# SensorBoard.net
KiCad netlist of a schematic drawn in EAGLE
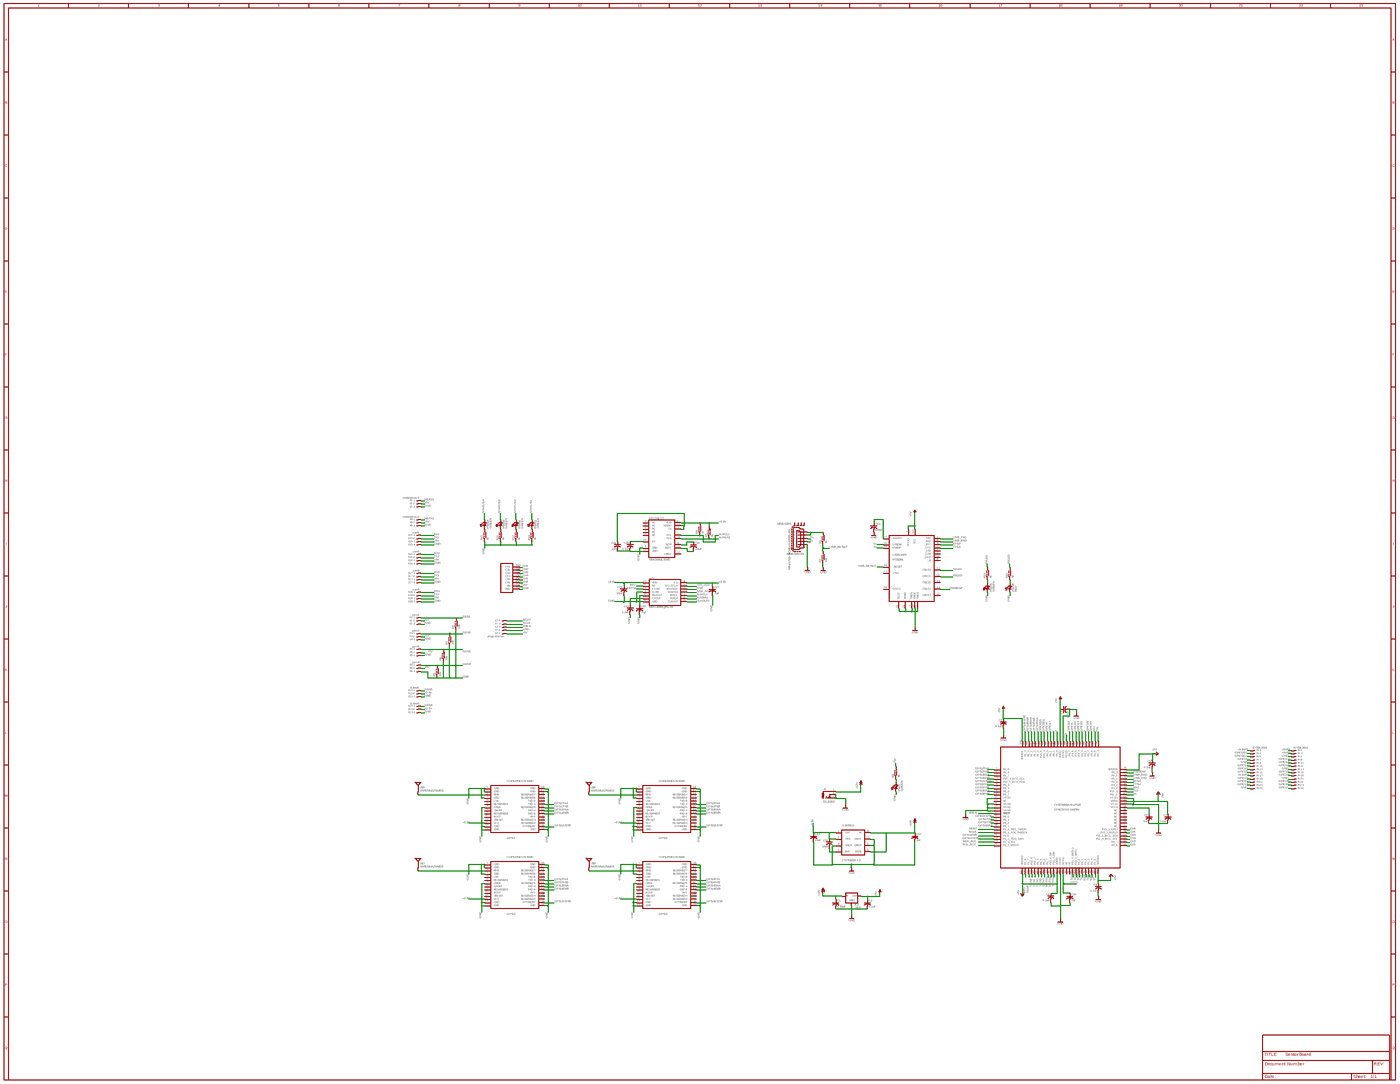
[diagram p0: schematic, sheet 1, overview]
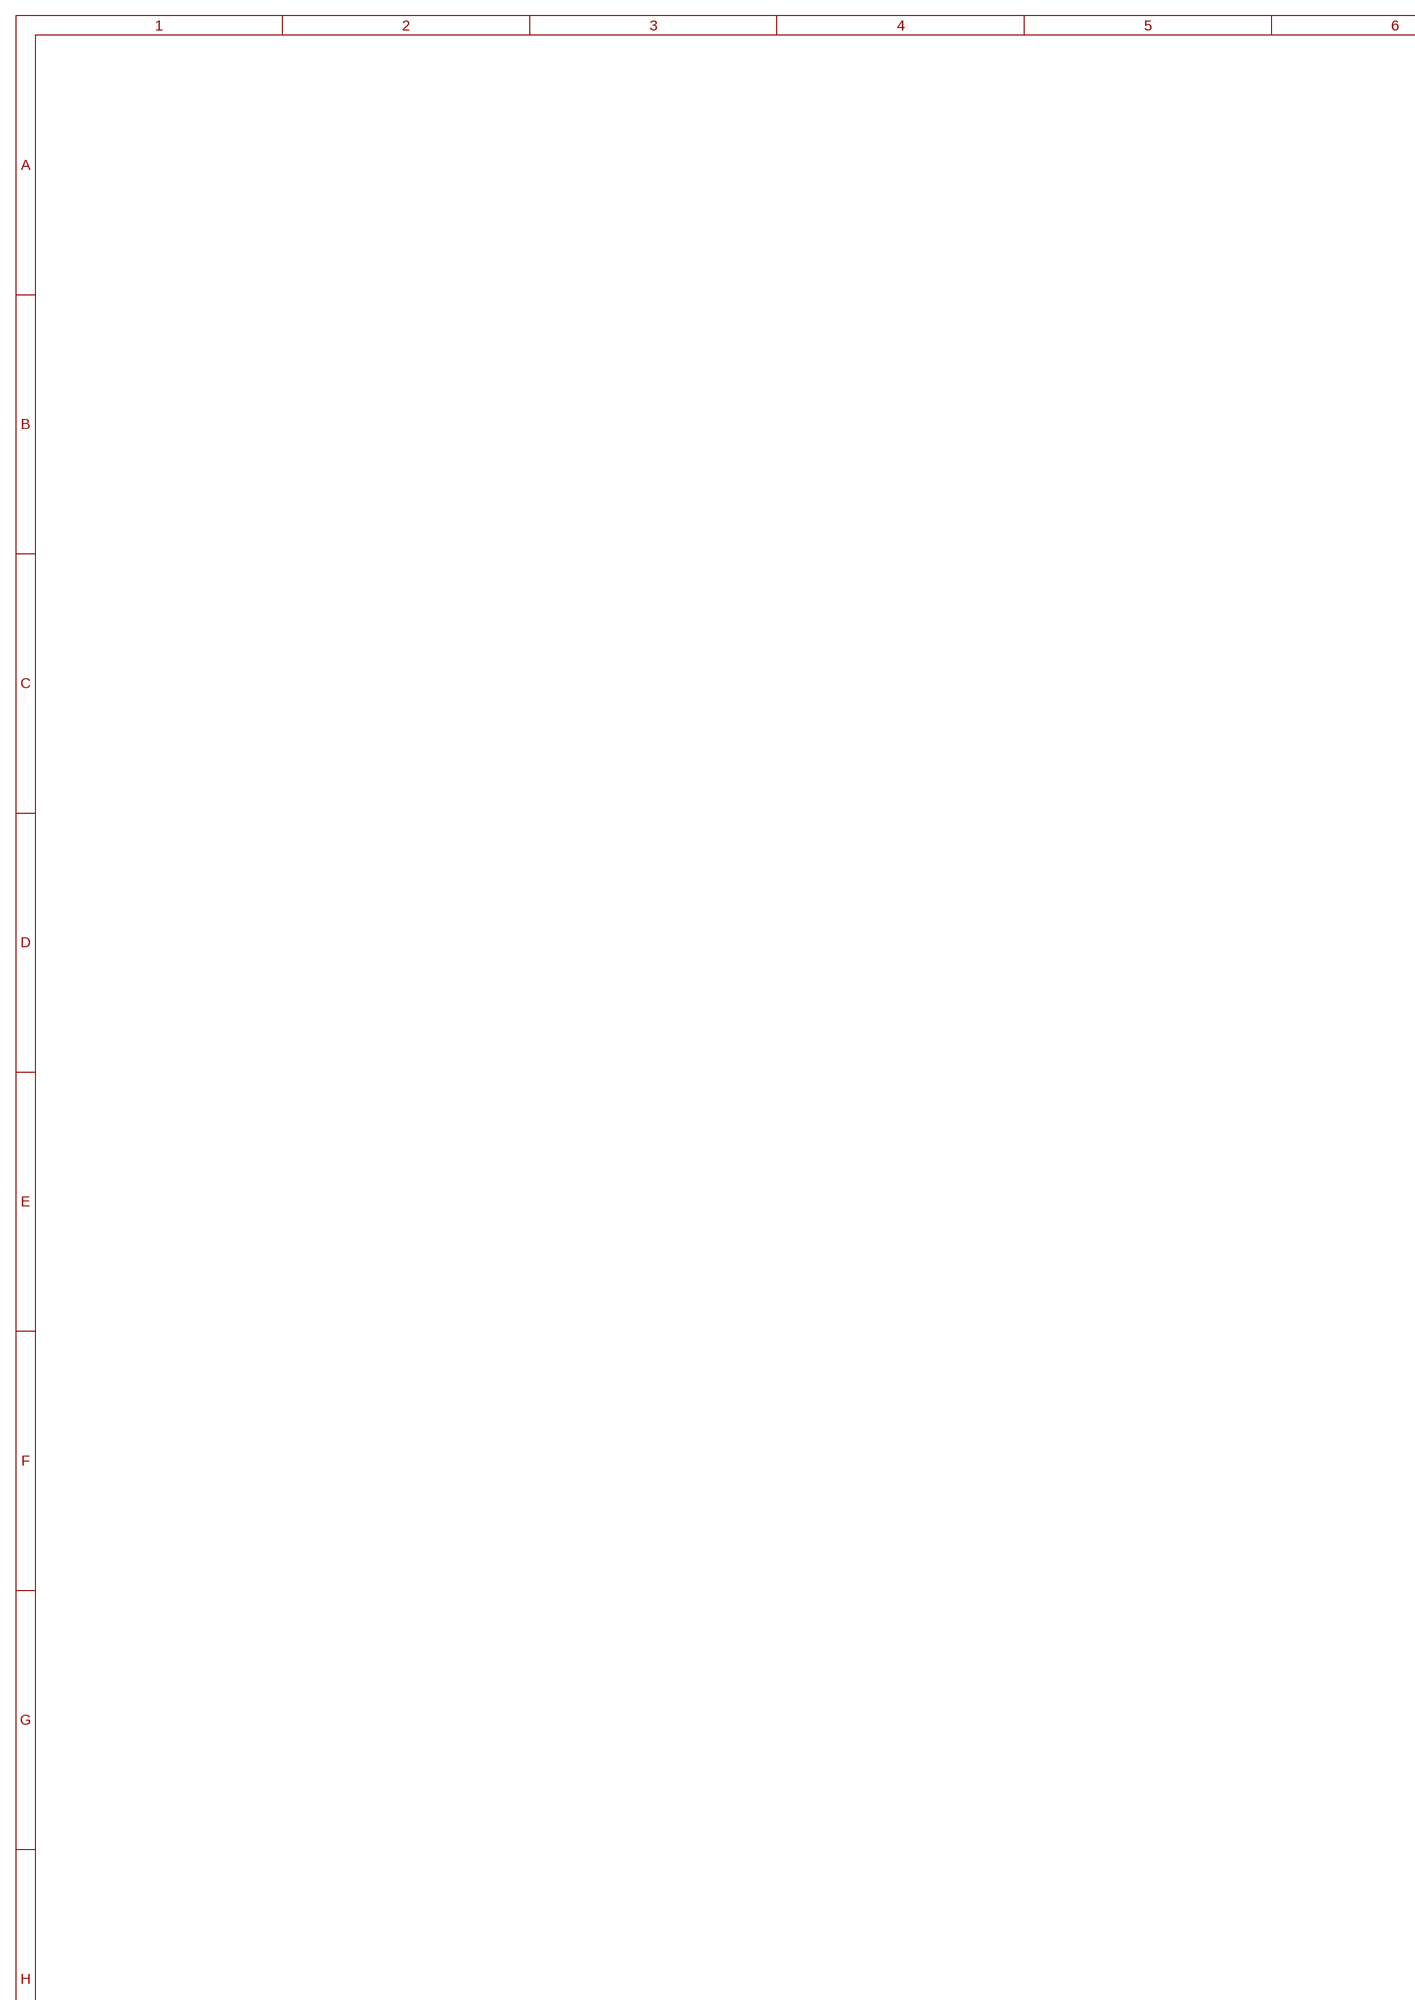
[diagram p1: schematic, sheet 1, part 1 of 8]
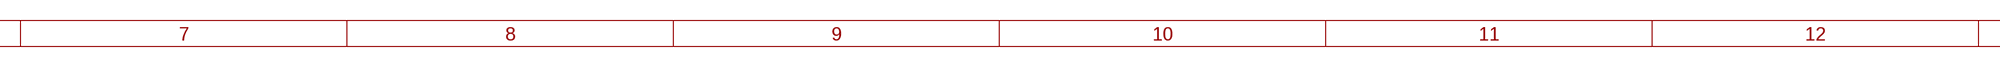
[diagram p2: schematic, sheet 1, part 2 of 8]
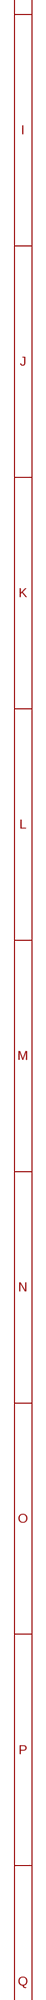
[diagram p3: schematic, sheet 1, part 3 of 8]
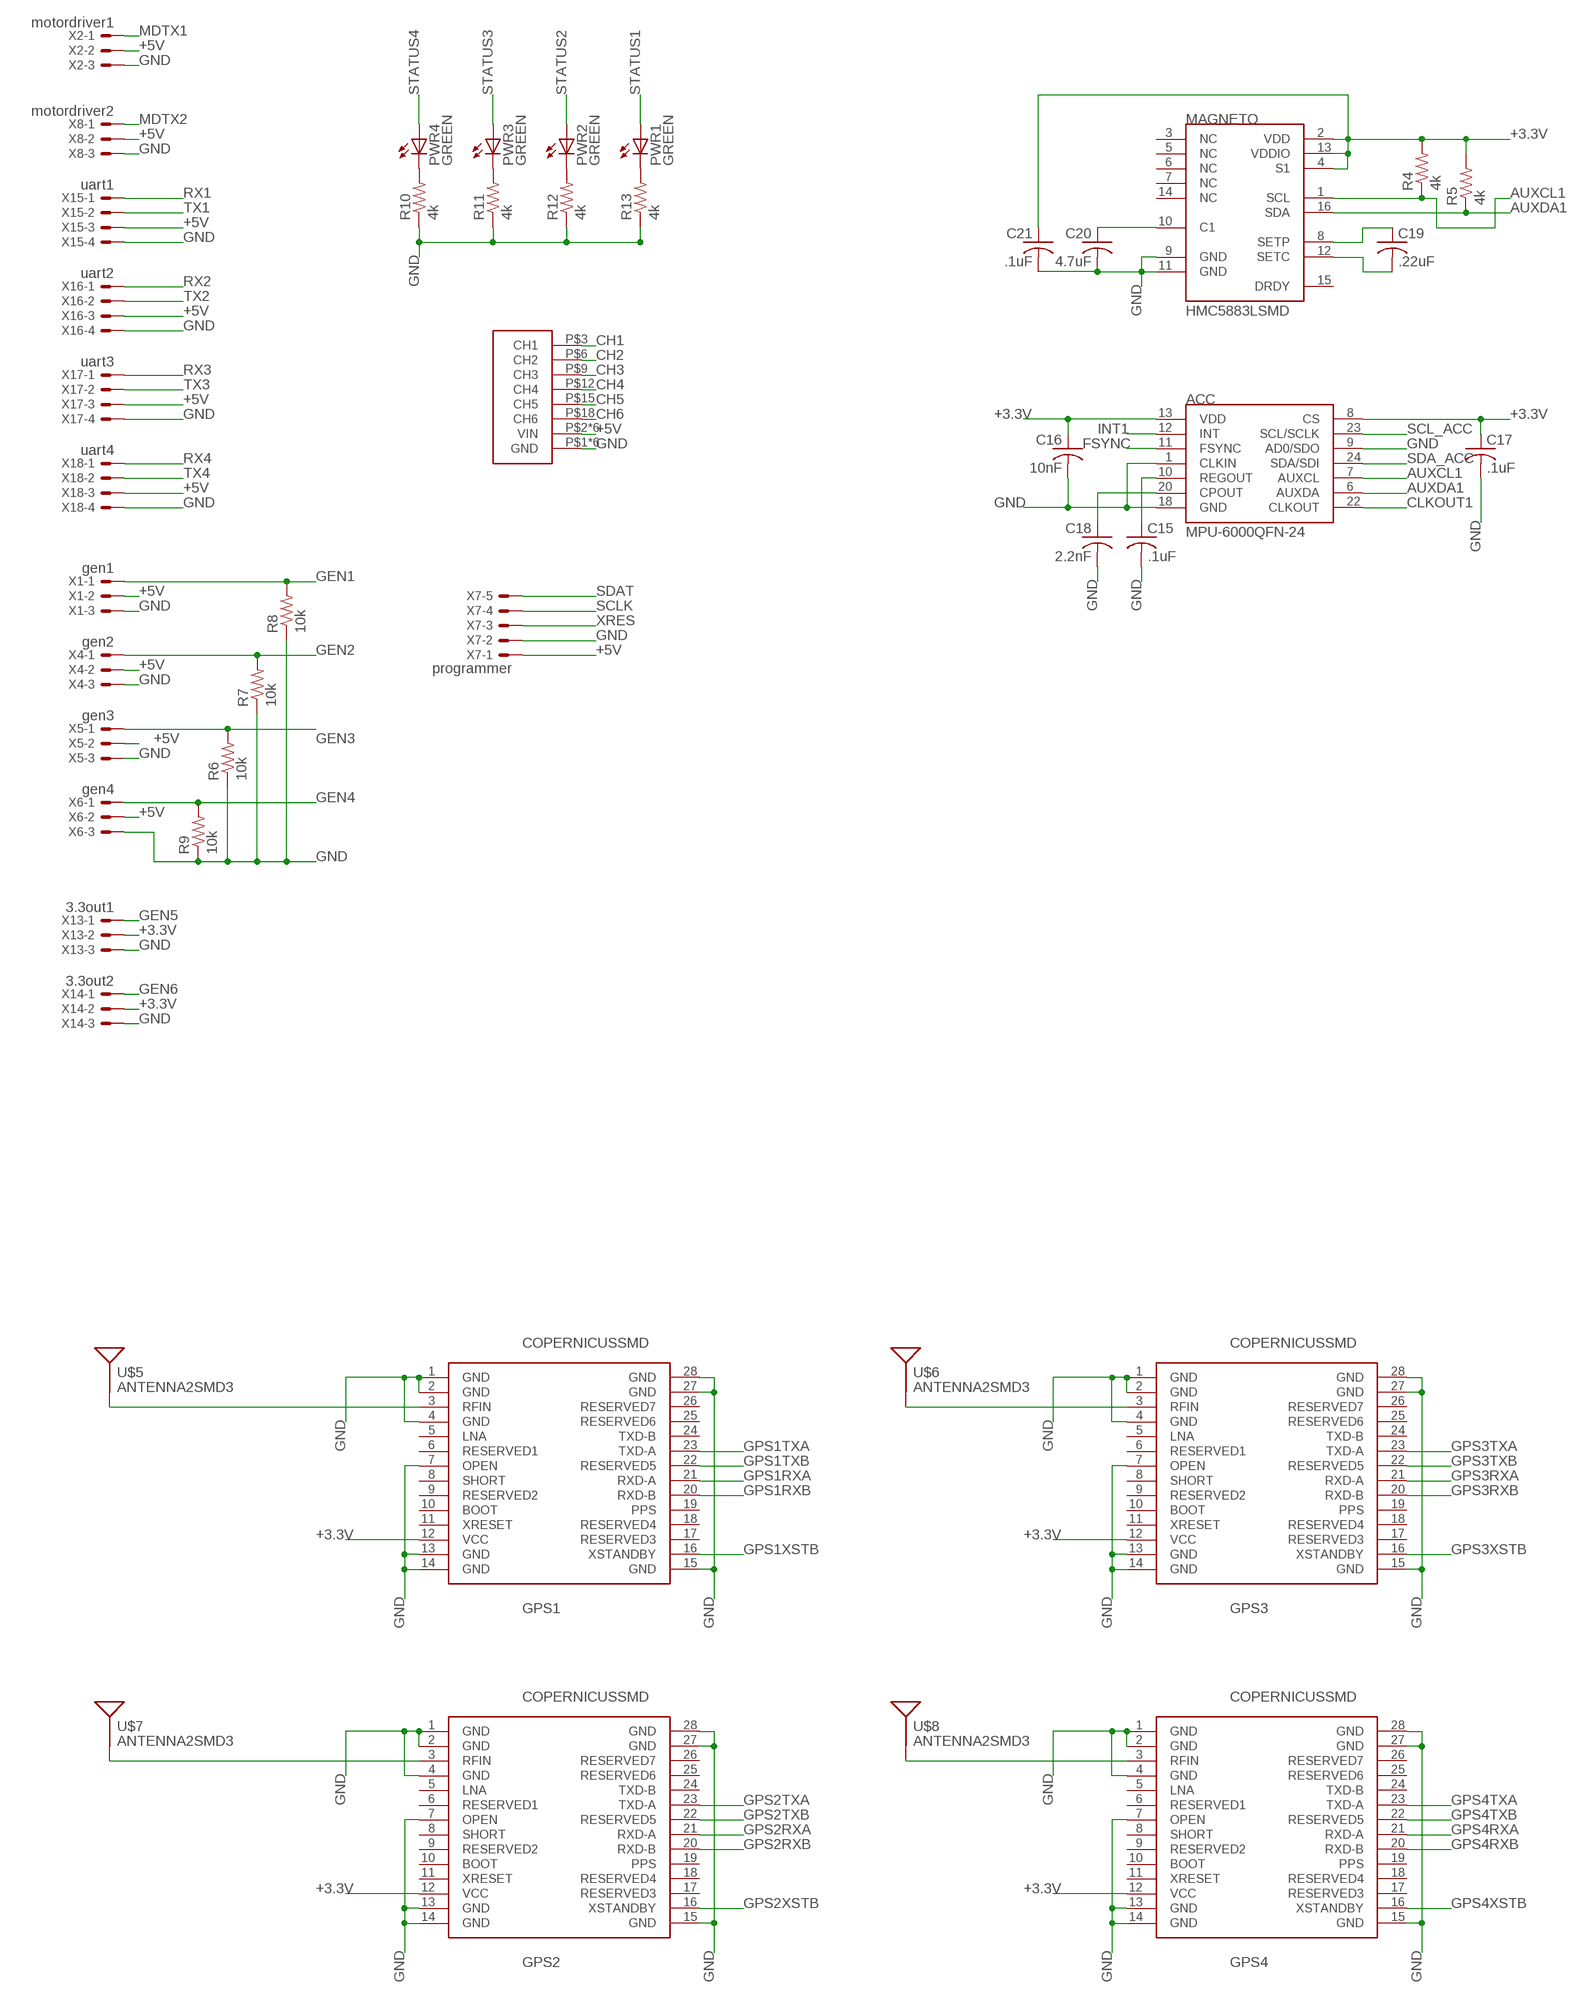
[diagram p4: schematic, sheet 1, part 4 of 8]
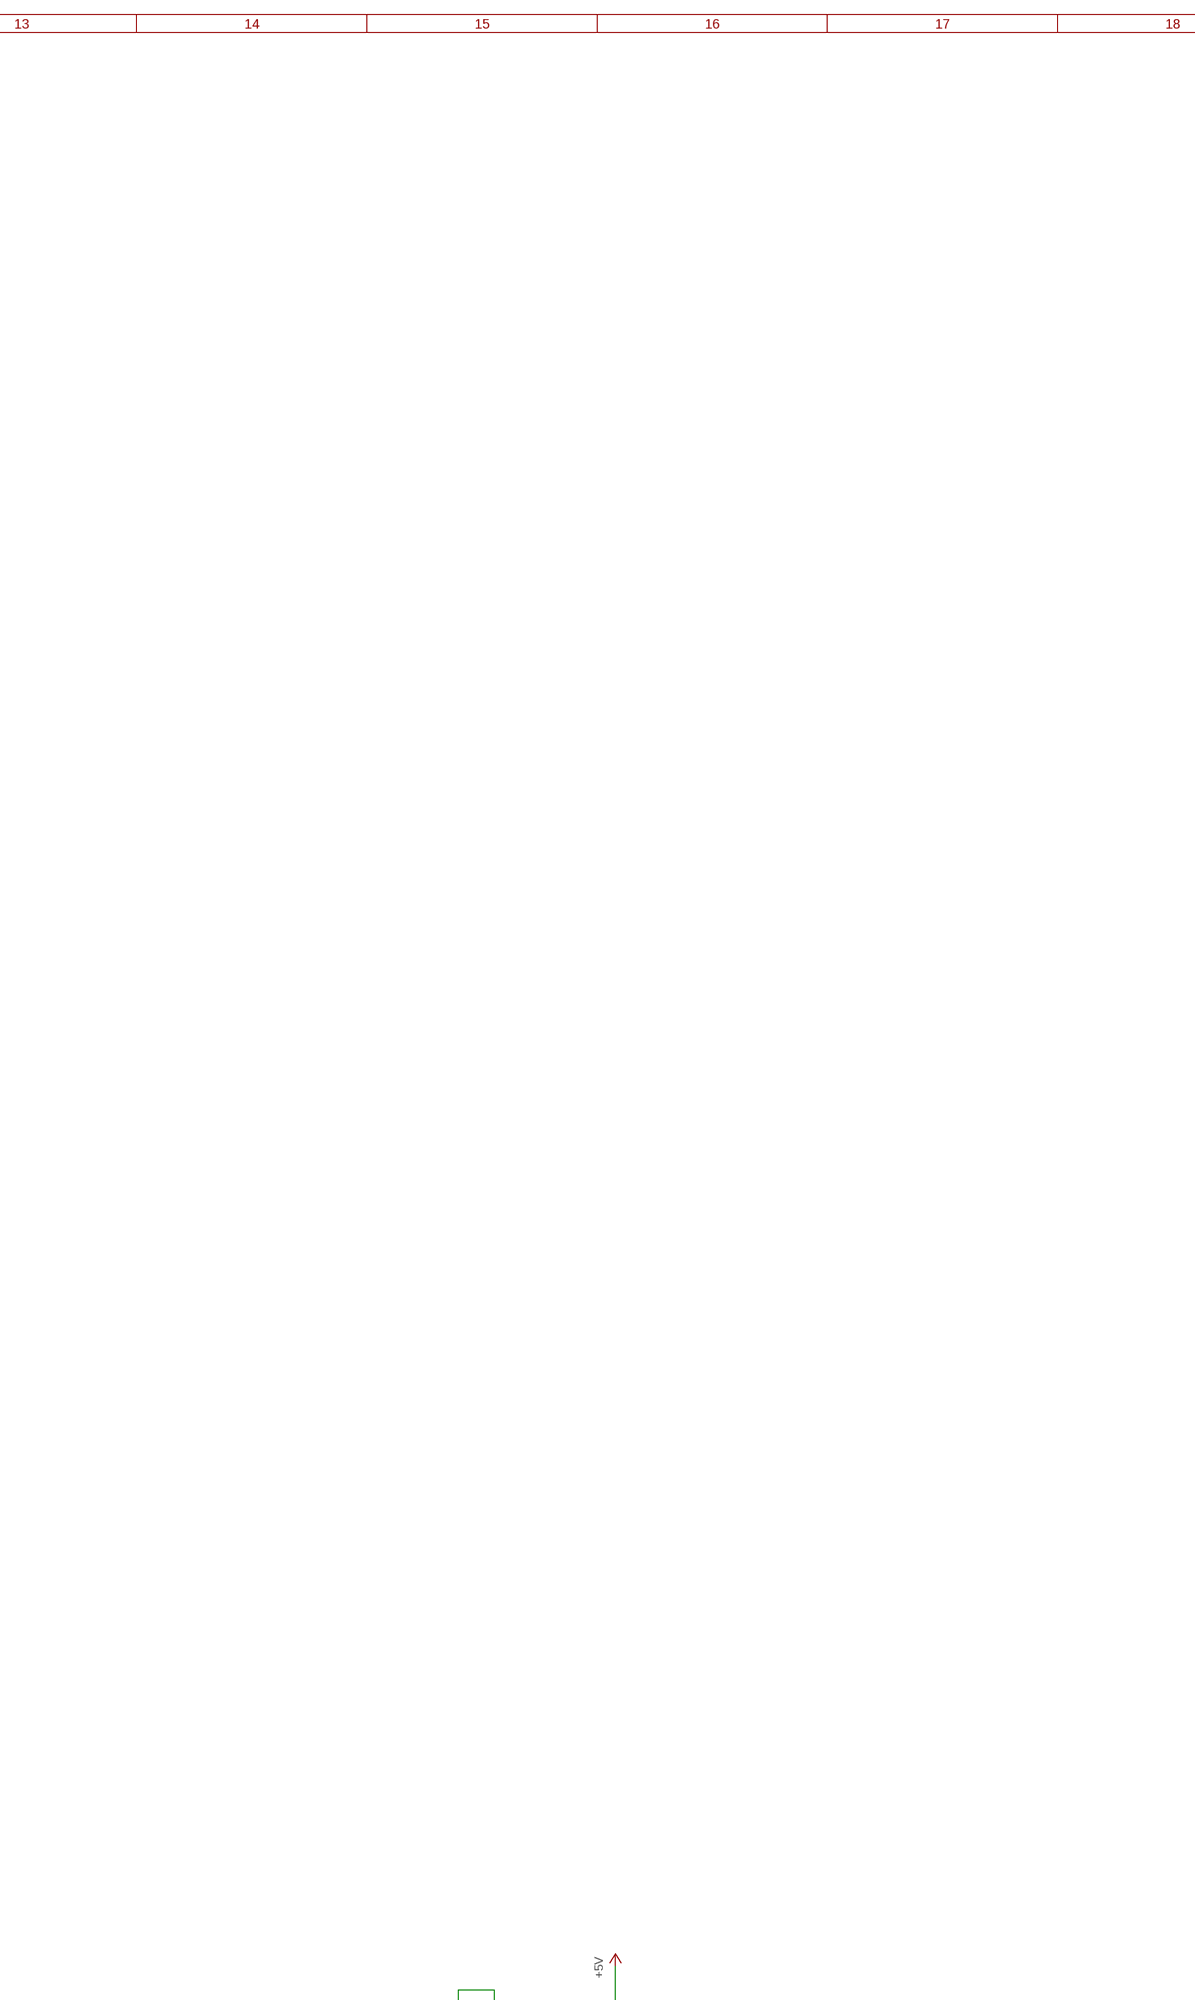
[diagram p5: schematic, sheet 1, part 5 of 8]
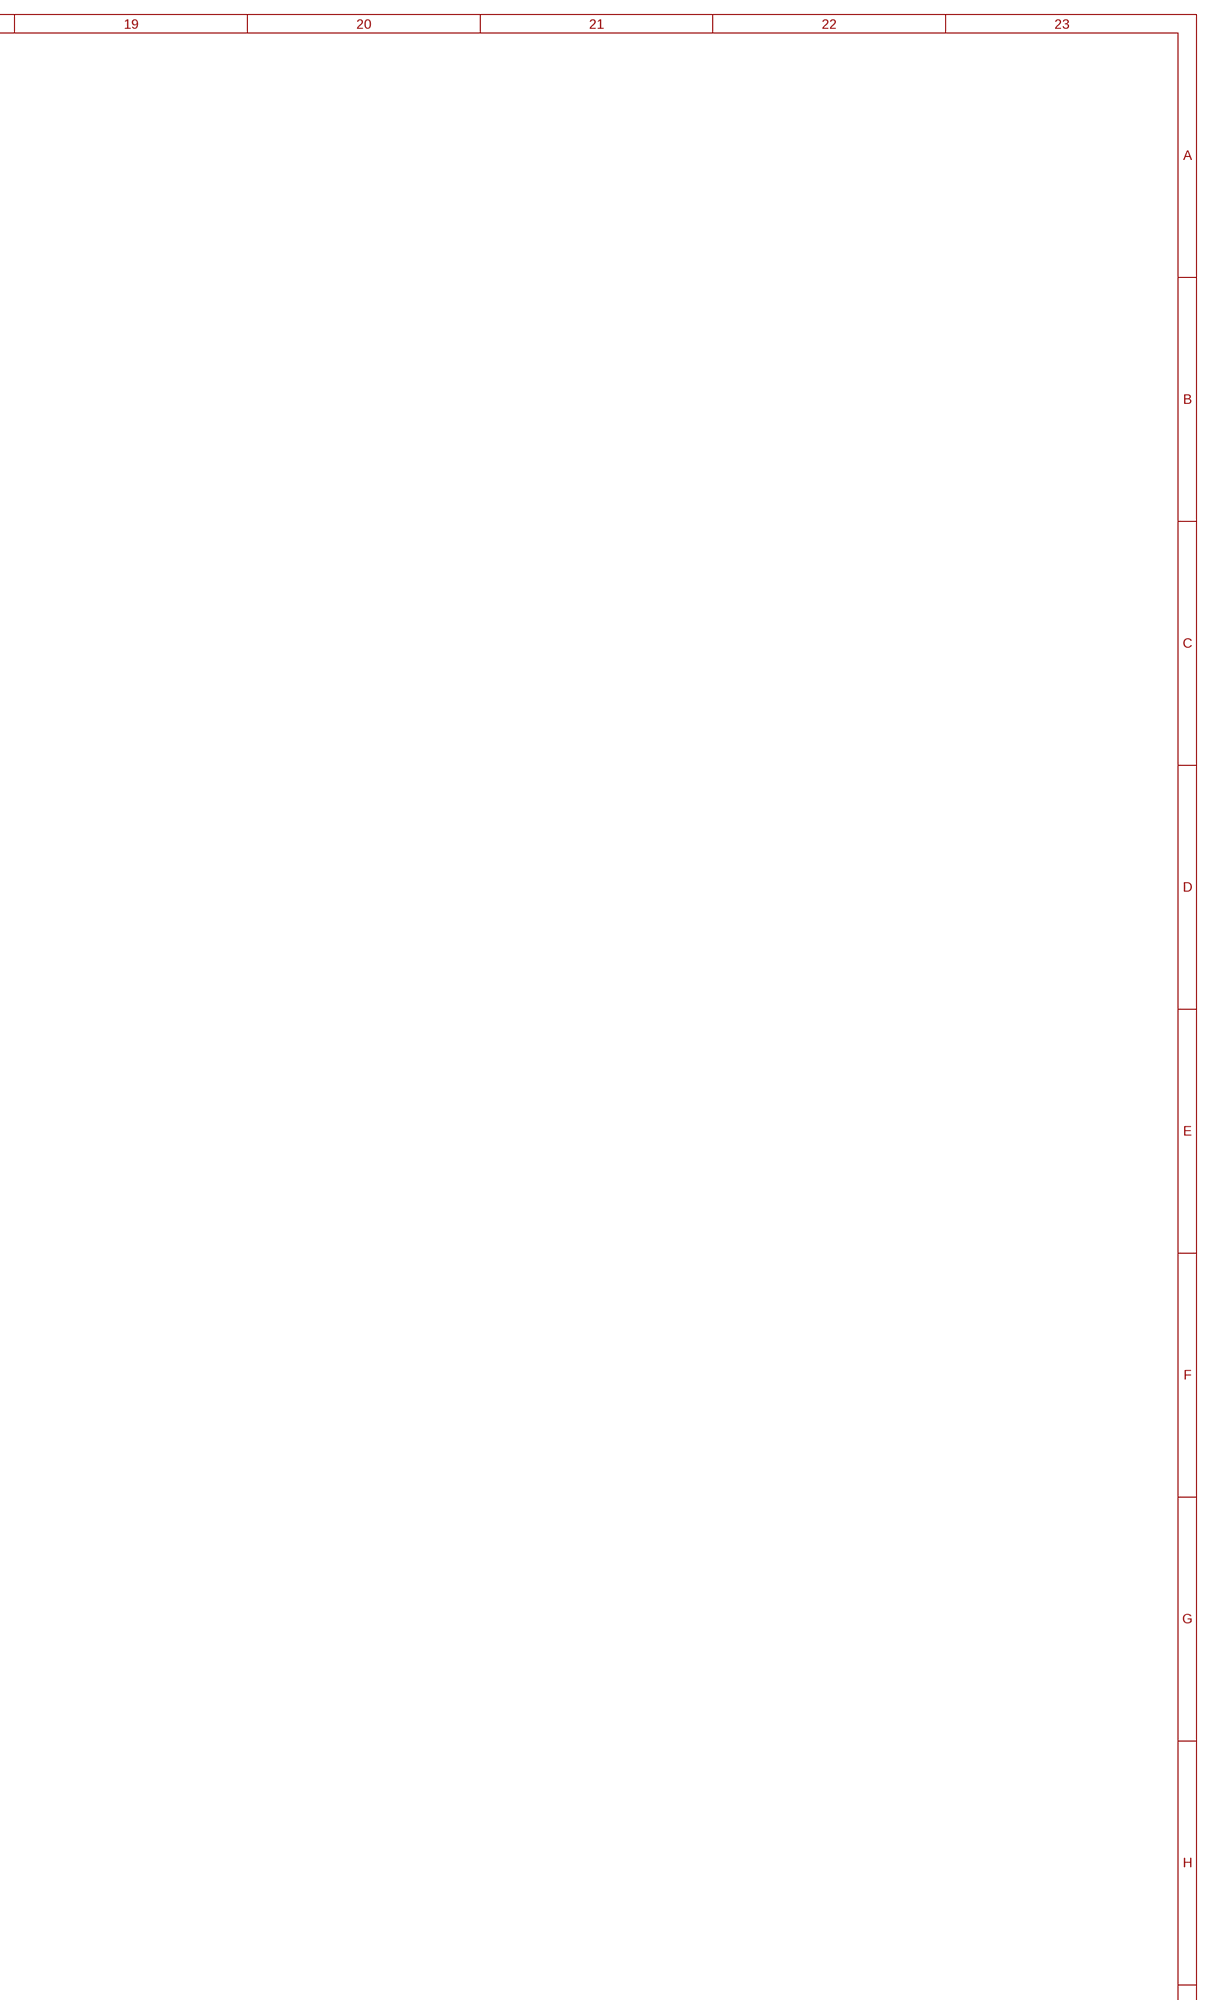
[diagram p6: schematic, sheet 1, part 6 of 8]
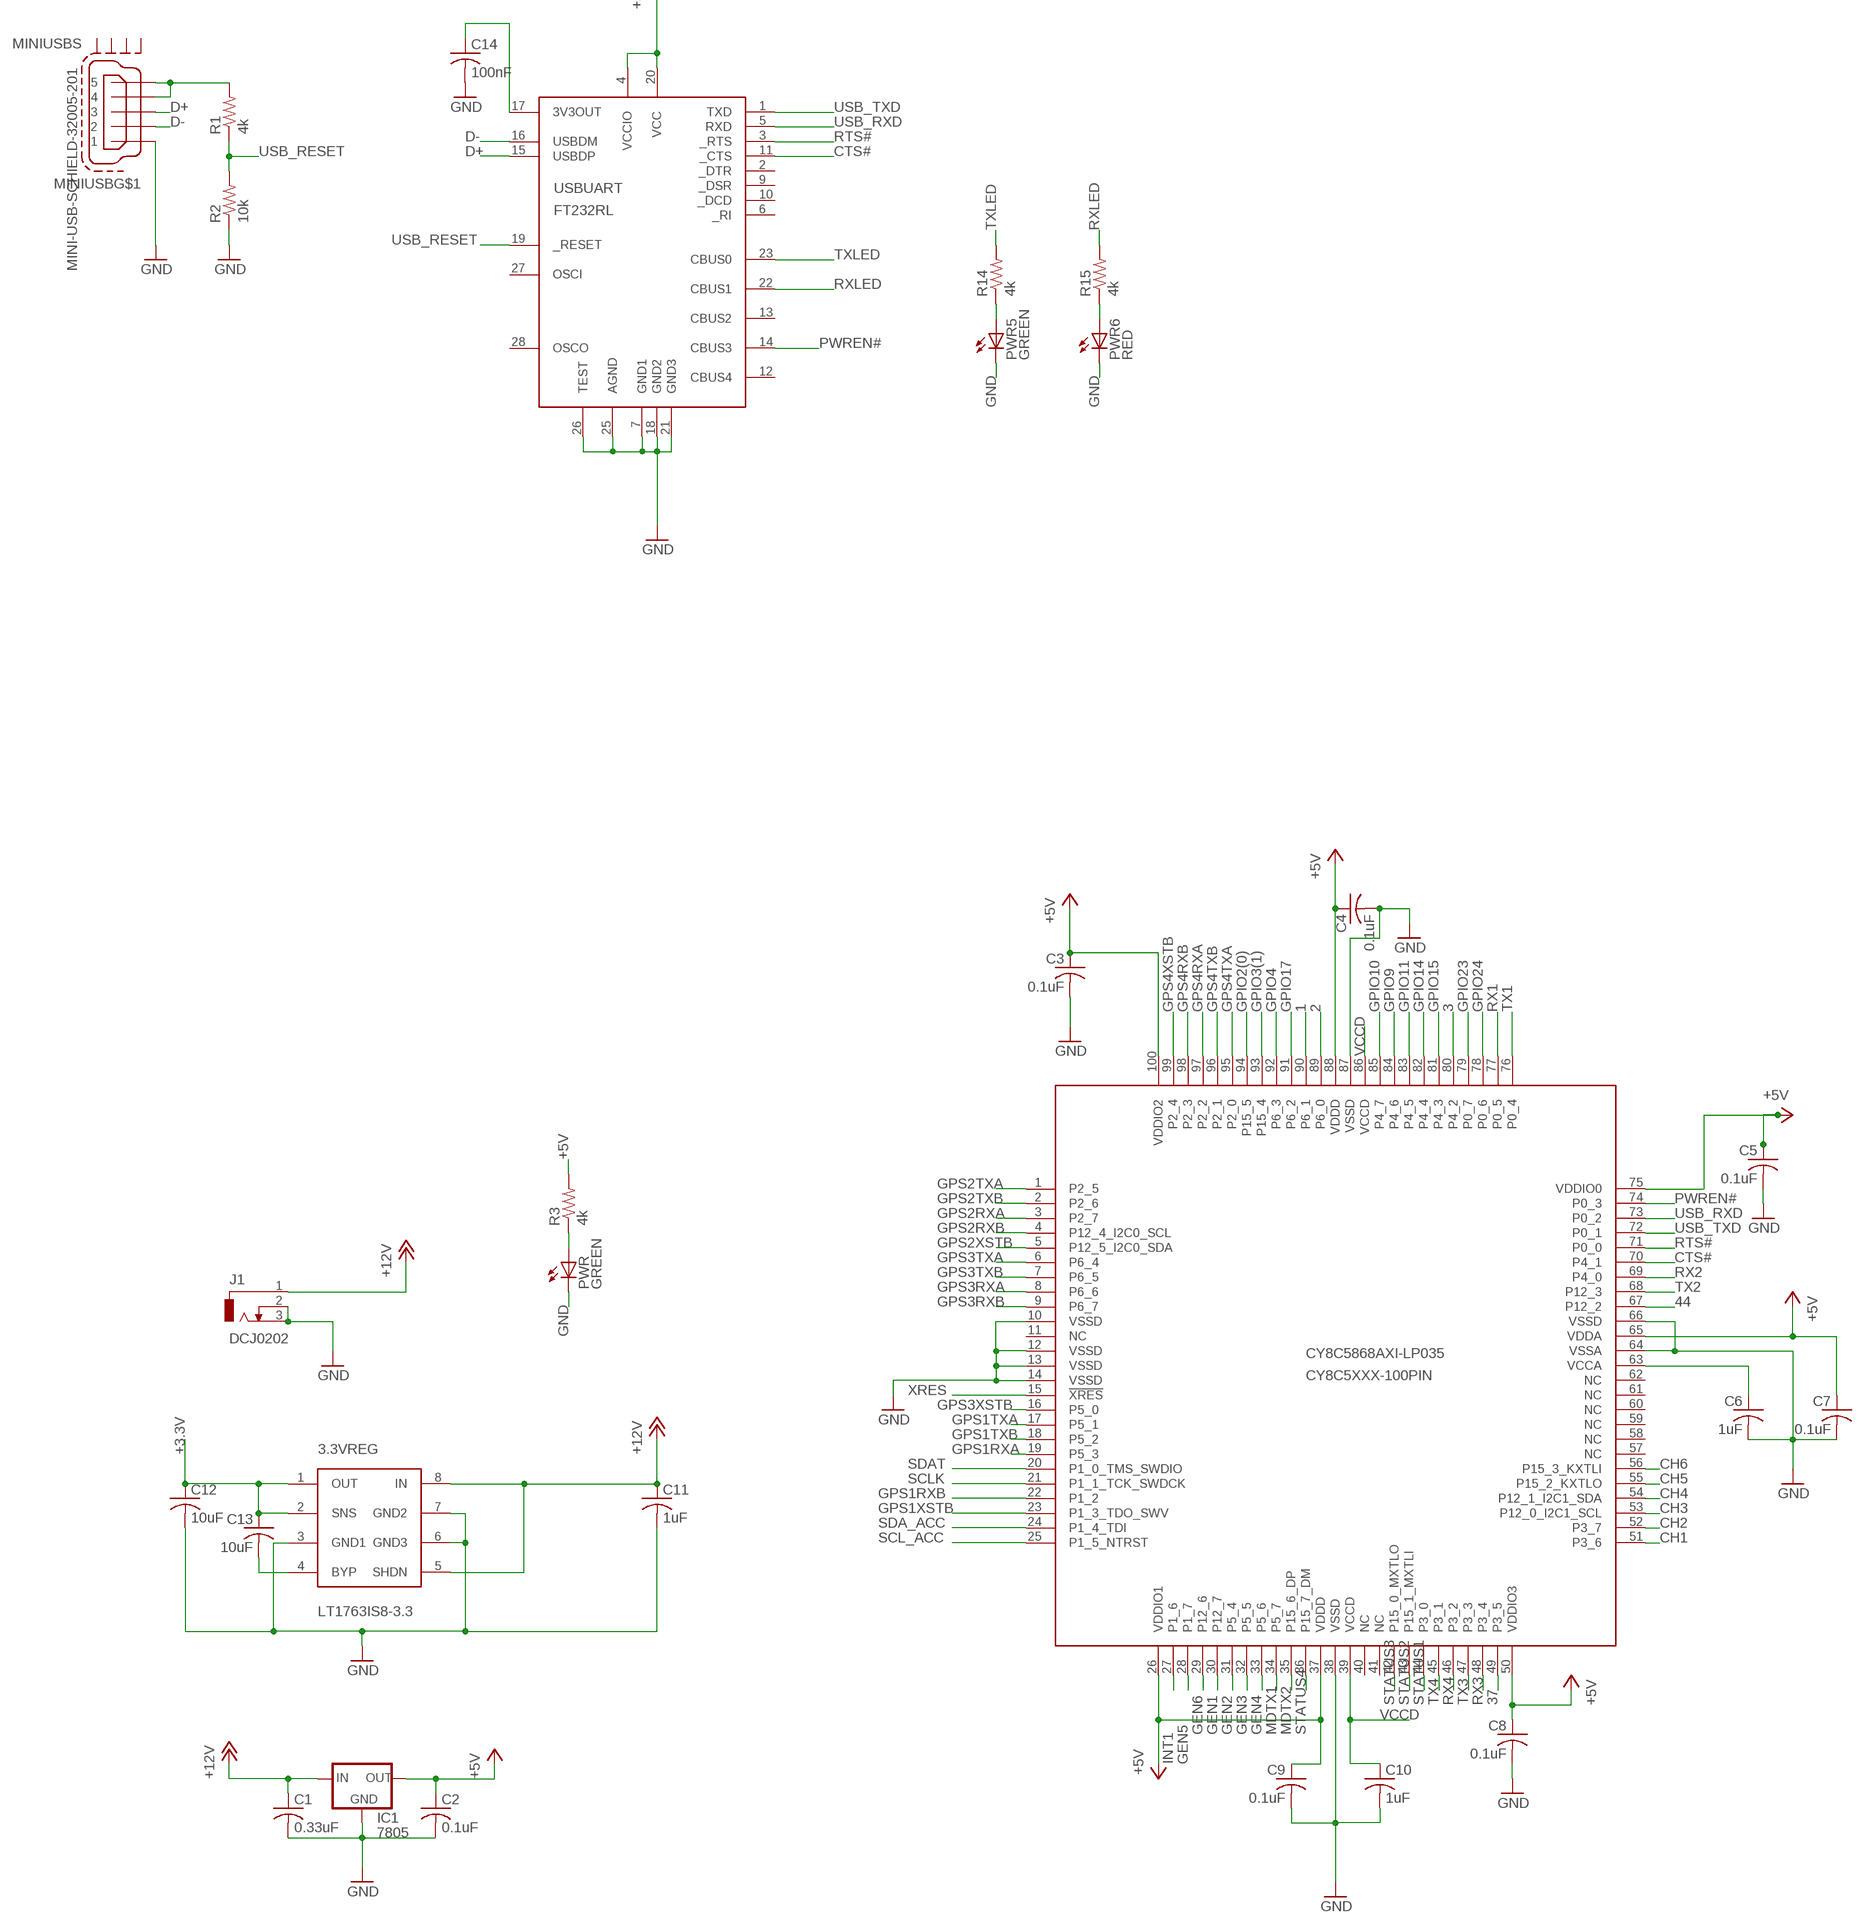
[diagram p7: schematic, sheet 1, part 7 of 8]
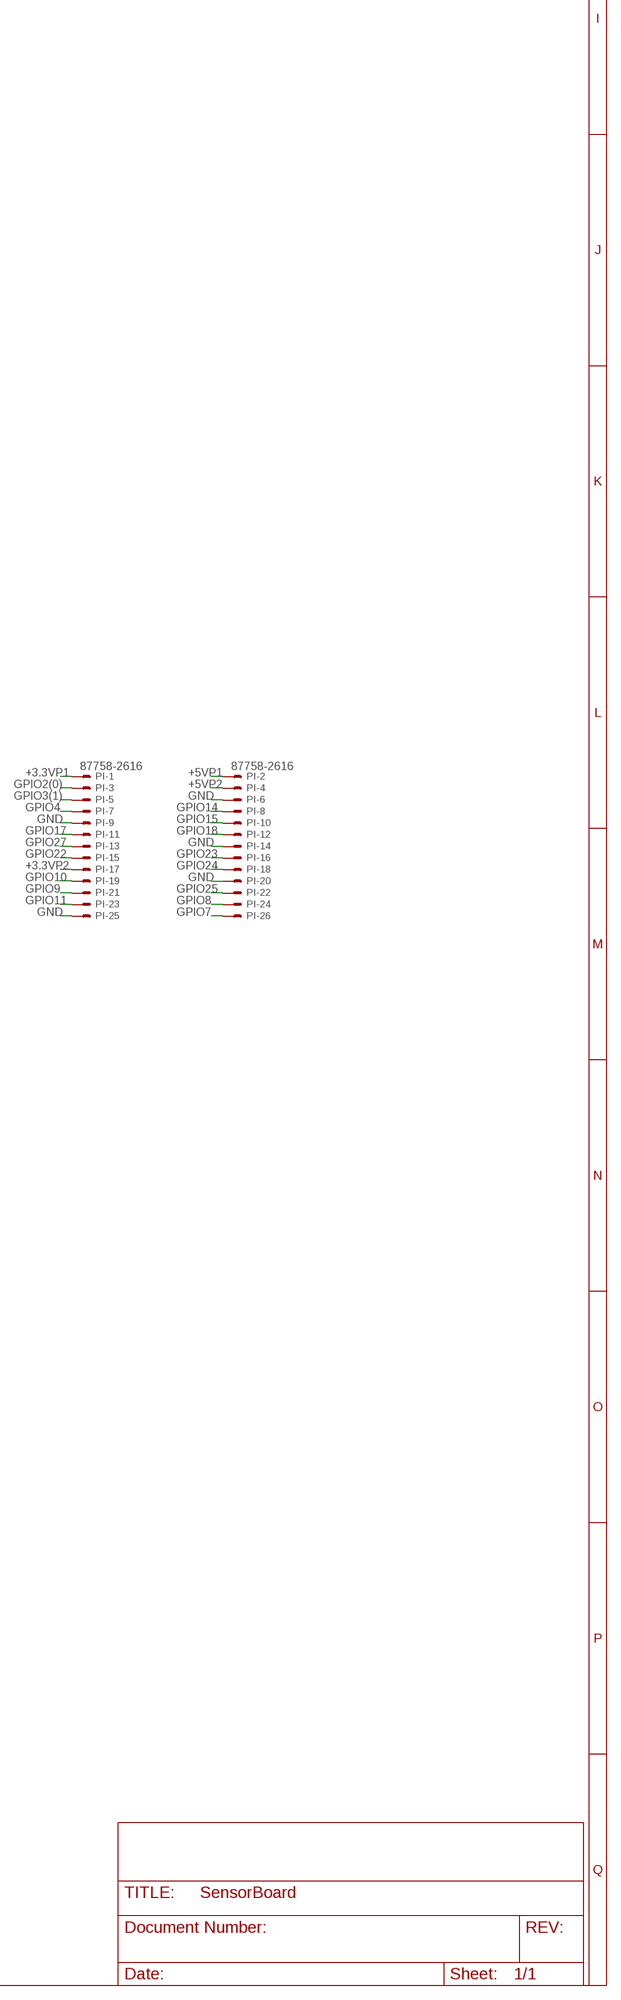
[diagram p8: schematic, sheet 1, part 8 of 8]

(export (version "E")
  (design (tool "Eeschema 10.0.6"))
  (components
    (comp (ref "3.3VREG")
      (value "LT1763IS8-3.3")
      (footprint "eagle-import:LT1763IS8-SMD")
      (libsource (lib "eagle-import") (part "LT1763IS8"))
    )
    (comp (ref "ACC")
      (value "MPU-6000QFN-24")
      (footprint "eagle-import:QFN-24-TESTING")
      (libsource (lib "eagle-import") (part "MPU-6000QFN-24"))
    )
    (comp (ref "C1")
      (value "0.33uF")
      (footprint "eagle-import:C0402")
      (libsource (lib "eagle-import") (part "C-USC0402"))
    )
    (comp (ref "C2")
      (value "0.1uF")
      (footprint "eagle-import:C0402")
      (libsource (lib "eagle-import") (part "C-USC0402"))
    )
    (comp (ref "C3")
      (value "0.1uF")
      (footprint "eagle-import:C0402")
      (libsource (lib "eagle-import") (part "C-USC0402"))
    )
    (comp (ref "C4")
      (value "0.1uF")
      (footprint "eagle-import:C0402")
      (libsource (lib "eagle-import") (part "C-USC0402"))
    )
    (comp (ref "C5")
      (value "0.1uF")
      (footprint "eagle-import:C0402")
      (libsource (lib "eagle-import") (part "C-USC0402"))
    )
    (comp (ref "C6")
      (value "1uF")
      (footprint "eagle-import:C0402")
      (libsource (lib "eagle-import") (part "C-USC0402"))
    )
    (comp (ref "C7")
      (value "0.1uF")
      (footprint "eagle-import:C0402")
      (libsource (lib "eagle-import") (part "C-USC0402"))
    )
    (comp (ref "C8")
      (value "0.1uF")
      (footprint "eagle-import:C0402")
      (libsource (lib "eagle-import") (part "C-USC0402"))
    )
    (comp (ref "C9")
      (value "0.1uF")
      (footprint "eagle-import:C0402")
      (libsource (lib "eagle-import") (part "C-USC0402"))
    )
    (comp (ref "C10")
      (value "1uF")
      (footprint "eagle-import:C0402")
      (libsource (lib "eagle-import") (part "C-USC0402"))
    )
    (comp (ref "C11")
      (value "1uF")
      (footprint "eagle-import:C0402")
      (libsource (lib "eagle-import") (part "C-USC0402"))
    )
    (comp (ref "C12")
      (value "10uF")
      (footprint "eagle-import:C0402")
      (libsource (lib "eagle-import") (part "C-USC0402"))
    )
    (comp (ref "C13")
      (value "10uF")
      (footprint "eagle-import:C0402")
      (libsource (lib "eagle-import") (part "C-USC0402"))
    )
    (comp (ref "C14")
      (value "100nF")
      (footprint "eagle-import:C0402")
      (libsource (lib "eagle-import") (part "C-USC0402"))
    )
    (comp (ref "C15")
      (value ".1uF")
      (footprint "eagle-import:C0402")
      (libsource (lib "eagle-import") (part "C-USC0402"))
    )
    (comp (ref "C16")
      (value "10nF")
      (footprint "eagle-import:C0402")
      (libsource (lib "eagle-import") (part "C-USC0402"))
    )
    (comp (ref "C17")
      (value ".1uF")
      (footprint "eagle-import:C0402")
      (libsource (lib "eagle-import") (part "C-USC0402"))
    )
    (comp (ref "C18")
      (value "2.2nF")
      (footprint "eagle-import:C0402")
      (libsource (lib "eagle-import") (part "C-USC0402"))
    )
    (comp (ref "C19")
      (value ".22uF")
      (footprint "eagle-import:C0402")
      (libsource (lib "eagle-import") (part "C-USC0402"))
    )
    (comp (ref "C20")
      (value "4.7uF")
      (footprint "eagle-import:C0402")
      (libsource (lib "eagle-import") (part "C-USC0402"))
    )
    (comp (ref "C21")
      (value ".1uF")
      (footprint "eagle-import:C0402")
      (libsource (lib "eagle-import") (part "C-USC0402"))
    )
    (comp (ref "CY8C5868AXI-LP035")
      (value "CY8C5XXX-100PIN")
      (footprint "eagle-import:TQFP-14X14-100")
      (fields (field (name "MPN") "CY8C5588AXI-060"))
      (libsource (lib "eagle-import") (part "CY8C5XXX-100PIN"))
    )
    (comp (ref "GPS1")
      (value "COPERNICUSSMD")
      (footprint "eagle-import:COPERNICUS")
      (libsource (lib "eagle-import") (part "COPERNICUSSMD"))
    )
    (comp (ref "GPS2")
      (value "COPERNICUSSMD")
      (footprint "eagle-import:COPERNICUS")
      (libsource (lib "eagle-import") (part "COPERNICUSSMD"))
    )
    (comp (ref "GPS3")
      (value "COPERNICUSSMD")
      (footprint "eagle-import:COPERNICUS")
      (libsource (lib "eagle-import") (part "COPERNICUSSMD"))
    )
    (comp (ref "GPS4")
      (value "COPERNICUSSMD")
      (footprint "eagle-import:COPERNICUS")
      (libsource (lib "eagle-import") (part "COPERNICUSSMD"))
    )
    (comp (ref "IC1")
      (value "7805")
      (footprint "eagle-import:78XXL")
      (libsource (lib "eagle-import") (part "78XXL"))
    )
    (comp (ref "J1")
      (value "DCJ0202")
      (footprint "eagle-import:DCJ0202")
      (libsource (lib "eagle-import") (part "DCJ0202"))
    )
    (comp (ref "MAGNETO")
      (value "HMC5883LSMD")
      (footprint "eagle-import:16LPCC")
      (libsource (lib "eagle-import") (part "HMC5883LSMD"))
    )
    (comp (ref "MINIUSB")
      (value "MINI-USB-SCHIELD-32005-201")
      (footprint "eagle-import:32005-201")
      (libsource (lib "eagle-import") (part "MINI-USB-SCHIELD-32005-201"))
    )
    (comp (ref "PI")
      (value "87758-2616")
      (footprint "eagle-import:87758-2616")
      (libsource (lib "eagle-import") (part "87758-2616"))
    )
    (comp (ref "PWR")
      (value "GREEN")
      (footprint "eagle-import:CHIP-LED0603")
      (libsource (lib "eagle-import") (part "LEDCHIP-LED0603"))
    )
    (comp (ref "PWR1")
      (value "GREEN")
      (footprint "eagle-import:CHIP-LED0603")
      (libsource (lib "eagle-import") (part "LEDCHIP-LED0603"))
    )
    (comp (ref "PWR2")
      (value "GREEN")
      (footprint "eagle-import:CHIP-LED0603")
      (libsource (lib "eagle-import") (part "LEDCHIP-LED0603"))
    )
    (comp (ref "PWR3")
      (value "GREEN")
      (footprint "eagle-import:CHIP-LED0603")
      (libsource (lib "eagle-import") (part "LEDCHIP-LED0603"))
    )
    (comp (ref "PWR4")
      (value "GREEN")
      (footprint "eagle-import:CHIP-LED0603")
      (libsource (lib "eagle-import") (part "LEDCHIP-LED0603"))
    )
    (comp (ref "PWR5")
      (value "GREEN")
      (footprint "eagle-import:CHIP-LED0603")
      (libsource (lib "eagle-import") (part "LEDCHIP-LED0603"))
    )
    (comp (ref "PWR6")
      (value "RED")
      (footprint "eagle-import:CHIP-LED0603")
      (libsource (lib "eagle-import") (part "LEDCHIP-LED0603"))
    )
    (comp (ref "R1")
      (value "4k")
      (footprint "eagle-import:0204_5")
      (libsource (lib "eagle-import") (part "R-US_0204/5"))
    )
    (comp (ref "R2")
      (value "10k")
      (footprint "eagle-import:0204_5")
      (libsource (lib "eagle-import") (part "R-US_0204/5"))
    )
    (comp (ref "R3")
      (value "4k")
      (footprint "eagle-import:0204_5")
      (libsource (lib "eagle-import") (part "R-US_0204/5"))
    )
    (comp (ref "R4")
      (value "4k")
      (footprint "eagle-import:0204_5")
      (libsource (lib "eagle-import") (part "R-US_0204/5"))
    )
    (comp (ref "R5")
      (value "4k")
      (footprint "eagle-import:0204_5")
      (libsource (lib "eagle-import") (part "R-US_0204/5"))
    )
    (comp (ref "R6")
      (value "10k")
      (footprint "eagle-import:0204_5")
      (libsource (lib "eagle-import") (part "R-US_0204/5"))
    )
    (comp (ref "R7")
      (value "10k")
      (footprint "eagle-import:0204_5")
      (libsource (lib "eagle-import") (part "R-US_0204/5"))
    )
    (comp (ref "R8")
      (value "10k")
      (footprint "eagle-import:0204_5")
      (libsource (lib "eagle-import") (part "R-US_0204/5"))
    )
    (comp (ref "R9")
      (value "10k")
      (footprint "eagle-import:0204_5")
      (libsource (lib "eagle-import") (part "R-US_0204/5"))
    )
    (comp (ref "R10")
      (value "4k")
      (footprint "eagle-import:0204_5")
      (libsource (lib "eagle-import") (part "R-US_0204/5"))
    )
    (comp (ref "R11")
      (value "4k")
      (footprint "eagle-import:0204_5")
      (libsource (lib "eagle-import") (part "R-US_0204/5"))
    )
    (comp (ref "R12")
      (value "4k")
      (footprint "eagle-import:0204_5")
      (libsource (lib "eagle-import") (part "R-US_0204/5"))
    )
    (comp (ref "R13")
      (value "4k")
      (footprint "eagle-import:0204_5")
      (libsource (lib "eagle-import") (part "R-US_0204/5"))
    )
    (comp (ref "R14")
      (value "4k")
      (footprint "eagle-import:0204_5")
      (libsource (lib "eagle-import") (part "R-US_0204/5"))
    )
    (comp (ref "R15")
      (value "4k")
      (footprint "eagle-import:0204_5")
      (libsource (lib "eagle-import") (part "R-US_0204/5"))
    )
    (comp (ref "RC")
      (value "6-CHANNEL")
      (footprint "eagle-import:6-CHANNEL")
      (libsource (lib "eagle-import") (part "6-CHANNEL"))
    )
    (comp (ref "U$5")
      (value "ANTENNA2SMD3")
      (footprint "eagle-import:ANTENNA-CHIP4")
      (libsource (lib "eagle-import") (part "ANTENNA2SMD3"))
    )
    (comp (ref "U$6")
      (value "ANTENNA2SMD3")
      (footprint "eagle-import:ANTENNA-CHIP4")
      (libsource (lib "eagle-import") (part "ANTENNA2SMD3"))
    )
    (comp (ref "U$7")
      (value "ANTENNA2SMD3")
      (footprint "eagle-import:ANTENNA-CHIP4")
      (libsource (lib "eagle-import") (part "ANTENNA2SMD3"))
    )
    (comp (ref "U$8")
      (value "ANTENNA2SMD3")
      (footprint "eagle-import:ANTENNA-CHIP4")
      (libsource (lib "eagle-import") (part "ANTENNA2SMD3"))
    )
    (comp (ref "USBUART")
      (value "FT232RL")
      (footprint "eagle-import:SSOP28DB")
      (libsource (lib "eagle-import") (part "FT232RL"))
    )
    (comp (ref "X1")
      (value "gen1")
      (footprint "eagle-import:KK-156-3")
      (libsource (lib "eagle-import") (part "KK-156-3"))
    )
    (comp (ref "X2")
      (value "motordriver1")
      (footprint "eagle-import:KK-156-3")
      (libsource (lib "eagle-import") (part "KK-156-3"))
    )
    (comp (ref "X4")
      (value "gen2")
      (footprint "eagle-import:KK-156-3")
      (libsource (lib "eagle-import") (part "KK-156-3"))
    )
    (comp (ref "X5")
      (value "gen3")
      (footprint "eagle-import:KK-156-3")
      (libsource (lib "eagle-import") (part "KK-156-3"))
    )
    (comp (ref "X6")
      (value "gen4")
      (footprint "eagle-import:KK-156-3")
      (libsource (lib "eagle-import") (part "KK-156-3"))
    )
    (comp (ref "X7")
      (value "programmer")
      (footprint "eagle-import:KK-156-5")
      (libsource (lib "eagle-import") (part "KK-156-5"))
    )
    (comp (ref "X8")
      (value "motordriver2")
      (footprint "eagle-import:KK-156-3")
      (libsource (lib "eagle-import") (part "KK-156-3"))
    )
    (comp (ref "X13")
      (value "3.3out1")
      (footprint "eagle-import:KK-156-3")
      (libsource (lib "eagle-import") (part "KK-156-3"))
    )
    (comp (ref "X14")
      (value "3.3out2")
      (footprint "eagle-import:KK-156-3")
      (libsource (lib "eagle-import") (part "KK-156-3"))
    )
    (comp (ref "X15")
      (value "uart1")
      (footprint "eagle-import:KK-156-4")
      (libsource (lib "eagle-import") (part "KK-156-4"))
    )
    (comp (ref "X16")
      (value "uart2")
      (footprint "eagle-import:KK-156-4")
      (libsource (lib "eagle-import") (part "KK-156-4"))
    )
    (comp (ref "X17")
      (value "uart3")
      (footprint "eagle-import:KK-156-4")
      (libsource (lib "eagle-import") (part "KK-156-4"))
    )
    (comp (ref "X18")
      (value "uart4")
      (footprint "eagle-import:KK-156-4")
      (libsource (lib "eagle-import") (part "KK-156-4"))
    )
  )
  (nets
    (net (code "1") (name "+5V") (class "Default")
      (node (ref "C2") (pin "1") (pinfunction "1_1") (pintype "passive"))
      (node (ref "C3") (pin "1") (pinfunction "1_1") (pintype "passive"))
      (node (ref "C4") (pin "1") (pinfunction "1_1") (pintype "passive"))
      (node (ref "C5") (pin "1") (pinfunction "1_1") (pintype "passive"))
      (node (ref "C7") (pin "1") (pinfunction "1_1") (pintype "passive"))
      (node (ref "C8") (pin "1") (pinfunction "1_1") (pintype "passive"))
      (node (ref "C9") (pin "1") (pinfunction "1_1") (pintype "passive"))
      (node (ref "CY8C5868AXI-LP035") (pin "100") (pinfunction "VDDIO2_100") (pintype "passive"))
      (node (ref "CY8C5868AXI-LP035") (pin "26") (pinfunction "VDDIO1_26") (pintype "passive"))
      (node (ref "CY8C5868AXI-LP035") (pin "37") (pinfunction "VDDD_37") (pintype "passive"))
      (node (ref "CY8C5868AXI-LP035") (pin "50") (pinfunction "VDDIO3_50") (pintype "passive"))
      (node (ref "CY8C5868AXI-LP035") (pin "65") (pinfunction "VDDA_65") (pintype "passive"))
      (node (ref "CY8C5868AXI-LP035") (pin "75") (pinfunction "VDDIO0_75") (pintype "passive"))
      (node (ref "CY8C5868AXI-LP035") (pin "88") (pinfunction "VDDD_88") (pintype "passive"))
      (node (ref "IC1") (pin "OUT") (pinfunction "OUT_OUT") (pintype "passive"))
      (node (ref "R3") (pin "2") (pinfunction "2_2") (pintype "passive"))
      (node (ref "RC") (pin "P$11") (pinfunction "VIN_P$11") (pintype "bidirectional"))
      (node (ref "RC") (pin "P$14") (pinfunction "VIN_P$14") (pintype "bidirectional"))
      (node (ref "RC") (pin "P$17") (pinfunction "VIN_P$17") (pintype "bidirectional"))
      (node (ref "RC") (pin "P$2") (pinfunction "VIN_P$2") (pintype "bidirectional"))
      (node (ref "RC") (pin "P$5") (pinfunction "VIN_P$5") (pintype "bidirectional"))
      (node (ref "RC") (pin "P$8") (pinfunction "VIN_P$8") (pintype "bidirectional"))
      (node (ref "USBUART") (pin "20") (pinfunction "VCC_20") (pintype "power_in"))
      (node (ref "USBUART") (pin "4") (pinfunction "VCCIO_4") (pintype "power_in"))
      (node (ref "X1") (pin "2") (pinfunction "S_2") (pintype "passive"))
      (node (ref "X15") (pin "3") (pinfunction "S_3") (pintype "passive"))
      (node (ref "X16") (pin "3") (pinfunction "S_3") (pintype "passive"))
      (node (ref "X17") (pin "3") (pinfunction "S_3") (pintype "passive"))
      (node (ref "X18") (pin "3") (pinfunction "S_3") (pintype "passive"))
      (node (ref "X2") (pin "2") (pinfunction "S_2") (pintype "passive"))
      (node (ref "X4") (pin "2") (pinfunction "S_2") (pintype "passive"))
      (node (ref "X5") (pin "2") (pinfunction "S_2") (pintype "passive"))
      (node (ref "X6") (pin "2") (pinfunction "S_2") (pintype "passive"))
      (node (ref "X7") (pin "1") (pinfunction "S_1") (pintype "passive"))
      (node (ref "X8") (pin "2") (pinfunction "S_2") (pintype "passive"))
    )
    (net (code "2") (name "+12V") (class "Default")
      (node (ref "3.3VREG") (pin "5") (pinfunction "SHDN_5") (pintype "bidirectional"))
      (node (ref "3.3VREG") (pin "8") (pinfunction "IN_8") (pintype "bidirectional"))
      (node (ref "C1") (pin "1") (pinfunction "1_1") (pintype "passive"))
      (node (ref "C11") (pin "1") (pinfunction "1_1") (pintype "passive"))
      (node (ref "IC1") (pin "IN") (pinfunction "IN_IN") (pintype "input"))
      (node (ref "J1") (pin "1") (pinfunction "1_1") (pintype "passive"))
    )
    (net (code "3") (name "/+3.3V") (class "Default")
      (node (ref "3.3VREG") (pin "1") (pinfunction "OUT_1") (pintype "bidirectional"))
      (node (ref "3.3VREG") (pin "2") (pinfunction "SNS_2") (pintype "bidirectional"))
      (node (ref "ACC") (pin "13") (pinfunction "VDD_13") (pintype "bidirectional"))
      (node (ref "ACC") (pin "8") (pinfunction "CS_8") (pintype "bidirectional"))
      (node (ref "C12") (pin "1") (pinfunction "1_1") (pintype "passive"))
      (node (ref "C13") (pin "1") (pinfunction "1_1") (pintype "passive"))
      (node (ref "C16") (pin "1") (pinfunction "1_1") (pintype "passive"))
      (node (ref "C17") (pin "1") (pinfunction "1_1") (pintype "passive"))
      (node (ref "C21") (pin "1") (pinfunction "1_1") (pintype "passive"))
      (node (ref "GPS1") (pin "12") (pinfunction "VCC_12") (pintype "bidirectional"))
      (node (ref "GPS2") (pin "12") (pinfunction "VCC_12") (pintype "bidirectional"))
      (node (ref "GPS3") (pin "12") (pinfunction "VCC_12") (pintype "bidirectional"))
      (node (ref "GPS4") (pin "12") (pinfunction "VCC_12") (pintype "bidirectional"))
      (node (ref "MAGNETO") (pin "13") (pinfunction "VDDIO_13") (pintype "bidirectional"))
      (node (ref "MAGNETO") (pin "2") (pinfunction "VDD_2") (pintype "bidirectional"))
      (node (ref "MAGNETO") (pin "4") (pinfunction "S1_4") (pintype "bidirectional"))
      (node (ref "R4") (pin "2") (pinfunction "2_2") (pintype "passive"))
      (node (ref "R5") (pin "2") (pinfunction "2_2") (pintype "passive"))
      (node (ref "X13") (pin "2") (pinfunction "S_2") (pintype "passive"))
      (node (ref "X14") (pin "2") (pinfunction "S_2") (pintype "passive"))
    )
    (net (code "4") (name "/+3.3VP1") (class "Default")
      (node (ref "PI") (pin "1") (pinfunction "S_1") (pintype "passive"))
    )
    (net (code "5") (name "/+3.3VP2") (class "Default")
      (node (ref "PI") (pin "17") (pinfunction "S_17") (pintype "passive"))
    )
    (net (code "6") (name "/+5VP1") (class "Default")
      (node (ref "PI") (pin "2") (pinfunction "S_2") (pintype "passive"))
    )
    (net (code "7") (name "/+5VP2") (class "Default")
      (node (ref "PI") (pin "4") (pinfunction "S_4") (pintype "passive"))
    )
    (net (code "8") (name "/1") (class "Default")
      (node (ref "CY8C5868AXI-LP035") (pin "90") (pinfunction "P6_1_90") (pintype "passive"))
    )
    (net (code "9") (name "/2") (class "Default")
      (node (ref "CY8C5868AXI-LP035") (pin "89") (pinfunction "P6_0_89") (pintype "passive"))
    )
    (net (code "10") (name "/3") (class "Default")
      (node (ref "CY8C5868AXI-LP035") (pin "80") (pinfunction "P4_2_80") (pintype "passive"))
    )
    (net (code "11") (name "/37") (class "Default")
      (node (ref "CY8C5868AXI-LP035") (pin "49") (pinfunction "P3_5_49") (pintype "passive"))
    )
    (net (code "12") (name "/44") (class "Default")
      (node (ref "CY8C5868AXI-LP035") (pin "67") (pinfunction "P12_2_67") (pintype "passive"))
    )
    (net (code "13") (name "/AUXCL1") (class "Default")
      (node (ref "ACC") (pin "7") (pinfunction "AUXCL_7") (pintype "bidirectional"))
      (node (ref "MAGNETO") (pin "1") (pinfunction "SCL_1") (pintype "bidirectional"))
      (node (ref "R4") (pin "1") (pinfunction "1_1") (pintype "passive"))
    )
    (net (code "14") (name "/AUXDA1") (class "Default")
      (node (ref "ACC") (pin "6") (pinfunction "AUXDA_6") (pintype "bidirectional"))
      (node (ref "MAGNETO") (pin "16") (pinfunction "SDA_16") (pintype "bidirectional"))
      (node (ref "R5") (pin "1") (pinfunction "1_1") (pintype "passive"))
    )
    (net (code "15") (name "/CH1") (class "Default")
      (node (ref "CY8C5868AXI-LP035") (pin "51") (pinfunction "P3_6_51") (pintype "passive"))
      (node (ref "RC") (pin "P$3") (pinfunction "CH1_P$3") (pintype "bidirectional"))
    )
    (net (code "16") (name "/CH2") (class "Default")
      (node (ref "CY8C5868AXI-LP035") (pin "52") (pinfunction "P3_7_52") (pintype "passive"))
      (node (ref "RC") (pin "P$6") (pinfunction "CH2_P$6") (pintype "bidirectional"))
    )
    (net (code "17") (name "/CH3") (class "Default")
      (node (ref "CY8C5868AXI-LP035") (pin "53") (pinfunction "P12_0_I2C1_SCL_53") (pintype "passive"))
      (node (ref "RC") (pin "P$9") (pinfunction "CH3_P$9") (pintype "bidirectional"))
    )
    (net (code "18") (name "/CH4") (class "Default")
      (node (ref "CY8C5868AXI-LP035") (pin "54") (pinfunction "P12_1_I2C1_SDA_54") (pintype "passive"))
      (node (ref "RC") (pin "P$12") (pinfunction "CH4_P$12") (pintype "bidirectional"))
    )
    (net (code "19") (name "/CH5") (class "Default")
      (node (ref "CY8C5868AXI-LP035") (pin "55") (pinfunction "P15_2_KXTLO_55") (pintype "passive"))
      (node (ref "RC") (pin "P$15") (pinfunction "CH5_P$15") (pintype "bidirectional"))
    )
    (net (code "20") (name "/CH6") (class "Default")
      (node (ref "CY8C5868AXI-LP035") (pin "56") (pinfunction "P15_3_KXTLI_56") (pintype "passive"))
      (node (ref "RC") (pin "P$18") (pinfunction "CH6_P$18") (pintype "bidirectional"))
    )
    (net (code "21") (name "/CLKOUT1") (class "Default")
      (node (ref "ACC") (pin "22") (pinfunction "CLKOUT_22") (pintype "bidirectional"))
    )
    (net (code "22") (name "/CTS#") (class "Default")
      (node (ref "CY8C5868AXI-LP035") (pin "70") (pinfunction "P4_1_70") (pintype "passive"))
      (node (ref "USBUART") (pin "11") (pinfunction "_CTS_11") (pintype "input"))
    )
    (net (code "23") (name "/D+") (class "Default")
      (node (ref "MINIUSB") (pin "3") (pinfunction "3_3") (pintype "passive"))
      (node (ref "USBUART") (pin "15") (pinfunction "USBDP_15") (pintype "bidirectional"))
    )
    (net (code "24") (name "/D-") (class "Default")
      (node (ref "MINIUSB") (pin "2") (pinfunction "2_2") (pintype "passive"))
      (node (ref "USBUART") (pin "16") (pinfunction "USBDM_16") (pintype "bidirectional"))
    )
    (net (code "25") (name "/FSYNC") (class "Default")
      (node (ref "ACC") (pin "11") (pinfunction "FSYNC_11") (pintype "bidirectional"))
    )
    (net (code "26") (name "/GEN1") (class "Default")
      (node (ref "CY8C5868AXI-LP035") (pin "30") (pinfunction "P12_7_30") (pintype "passive"))
      (node (ref "R8") (pin "2") (pinfunction "2_2") (pintype "passive"))
      (node (ref "X1") (pin "1") (pinfunction "S_1") (pintype "passive"))
    )
    (net (code "27") (name "/GEN2") (class "Default")
      (node (ref "CY8C5868AXI-LP035") (pin "31") (pinfunction "P5_4_31") (pintype "passive"))
      (node (ref "R7") (pin "2") (pinfunction "2_2") (pintype "passive"))
      (node (ref "X4") (pin "1") (pinfunction "S_1") (pintype "passive"))
    )
    (net (code "28") (name "/GEN3") (class "Default")
      (node (ref "CY8C5868AXI-LP035") (pin "32") (pinfunction "P5_5_32") (pintype "passive"))
      (node (ref "R6") (pin "2") (pinfunction "2_2") (pintype "passive"))
      (node (ref "X5") (pin "1") (pinfunction "S_1") (pintype "passive"))
    )
    (net (code "29") (name "/GEN4") (class "Default")
      (node (ref "CY8C5868AXI-LP035") (pin "33") (pinfunction "P5_6_33") (pintype "passive"))
      (node (ref "R9") (pin "2") (pinfunction "2_2") (pintype "passive"))
      (node (ref "X6") (pin "1") (pinfunction "S_1") (pintype "passive"))
    )
    (net (code "30") (name "/GEN5") (class "Default")
      (node (ref "CY8C5868AXI-LP035") (pin "28") (pinfunction "P1_7_28") (pintype "passive"))
      (node (ref "X13") (pin "1") (pinfunction "S_1") (pintype "passive"))
    )
    (net (code "31") (name "/GEN6") (class "Default")
      (node (ref "CY8C5868AXI-LP035") (pin "29") (pinfunction "P12_6_29") (pintype "passive"))
      (node (ref "X14") (pin "1") (pinfunction "S_1") (pintype "passive"))
    )
    (net (code "32") (name "/GPIO2(0)") (class "Default")
      (node (ref "CY8C5868AXI-LP035") (pin "94") (pinfunction "P15_5_94") (pintype "passive"))
      (node (ref "PI") (pin "3") (pinfunction "S_3") (pintype "passive"))
    )
    (net (code "33") (name "/GPIO3(1)") (class "Default")
      (node (ref "CY8C5868AXI-LP035") (pin "93") (pinfunction "P15_4_93") (pintype "passive"))
      (node (ref "PI") (pin "5") (pinfunction "S_5") (pintype "passive"))
    )
    (net (code "34") (name "/GPIO4") (class "Default")
      (node (ref "CY8C5868AXI-LP035") (pin "92") (pinfunction "P6_3_92") (pintype "passive"))
      (node (ref "PI") (pin "7") (pinfunction "S_7") (pintype "passive"))
    )
    (net (code "35") (name "/GPIO7") (class "Default")
      (node (ref "PI") (pin "26") (pinfunction "S_26") (pintype "passive"))
    )
    (net (code "36") (name "/GPIO8") (class "Default")
      (node (ref "PI") (pin "24") (pinfunction "S_24") (pintype "passive"))
    )
    (net (code "37") (name "/GPIO9") (class "Default")
      (node (ref "CY8C5868AXI-LP035") (pin "84") (pinfunction "P4_6_84") (pintype "passive"))
      (node (ref "PI") (pin "21") (pinfunction "S_21") (pintype "passive"))
    )
    (net (code "38") (name "/GPIO10") (class "Default")
      (node (ref "CY8C5868AXI-LP035") (pin "85") (pinfunction "P4_7_85") (pintype "passive"))
      (node (ref "PI") (pin "19") (pinfunction "S_19") (pintype "passive"))
    )
    (net (code "39") (name "/GPIO11") (class "Default")
      (node (ref "CY8C5868AXI-LP035") (pin "83") (pinfunction "P4_5_83") (pintype "passive"))
      (node (ref "PI") (pin "23") (pinfunction "S_23") (pintype "passive"))
    )
    (net (code "40") (name "/GPIO14") (class "Default")
      (node (ref "CY8C5868AXI-LP035") (pin "82") (pinfunction "P4_4_82") (pintype "passive"))
      (node (ref "PI") (pin "8") (pinfunction "S_8") (pintype "passive"))
    )
    (net (code "41") (name "/GPIO15") (class "Default")
      (node (ref "CY8C5868AXI-LP035") (pin "81") (pinfunction "P4_3_81") (pintype "passive"))
      (node (ref "PI") (pin "10") (pinfunction "S_10") (pintype "passive"))
    )
    (net (code "42") (name "/GPIO17") (class "Default")
      (node (ref "CY8C5868AXI-LP035") (pin "91") (pinfunction "P6_2_91") (pintype "passive"))
      (node (ref "PI") (pin "11") (pinfunction "S_11") (pintype "passive"))
    )
    (net (code "43") (name "/GPIO18") (class "Default")
      (node (ref "PI") (pin "12") (pinfunction "S_12") (pintype "passive"))
    )
    (net (code "44") (name "/GPIO22") (class "Default")
      (node (ref "PI") (pin "15") (pinfunction "S_15") (pintype "passive"))
    )
    (net (code "45") (name "/GPIO23") (class "Default")
      (node (ref "CY8C5868AXI-LP035") (pin "79") (pinfunction "P0_7_79") (pintype "passive"))
      (node (ref "PI") (pin "16") (pinfunction "S_16") (pintype "passive"))
    )
    (net (code "46") (name "/GPIO24") (class "Default")
      (node (ref "CY8C5868AXI-LP035") (pin "78") (pinfunction "P0_6_78") (pintype "passive"))
      (node (ref "PI") (pin "18") (pinfunction "S_18") (pintype "passive"))
    )
    (net (code "47") (name "/GPIO25") (class "Default")
      (node (ref "PI") (pin "22") (pinfunction "S_22") (pintype "passive"))
    )
    (net (code "48") (name "/GPIO27") (class "Default")
      (node (ref "PI") (pin "13") (pinfunction "S_13") (pintype "passive"))
    )
    (net (code "49") (name "/GPS1RXA") (class "Default")
      (node (ref "CY8C5868AXI-LP035") (pin "19") (pinfunction "P5_3_19") (pintype "passive"))
      (node (ref "GPS1") (pin "21") (pinfunction "RXD-A_21") (pintype "bidirectional"))
    )
    (net (code "50") (name "/GPS1RXB") (class "Default")
      (node (ref "CY8C5868AXI-LP035") (pin "22") (pinfunction "P1_2_22") (pintype "passive"))
      (node (ref "GPS1") (pin "20") (pinfunction "RXD-B_20") (pintype "bidirectional"))
    )
    (net (code "51") (name "/GPS1TXA") (class "Default")
      (node (ref "CY8C5868AXI-LP035") (pin "17") (pinfunction "P5_1_17") (pintype "passive"))
      (node (ref "GPS1") (pin "23") (pinfunction "TXD-A_23") (pintype "bidirectional"))
    )
    (net (code "52") (name "/GPS1TXB") (class "Default")
      (node (ref "CY8C5868AXI-LP035") (pin "18") (pinfunction "P5_2_18") (pintype "passive"))
      (node (ref "GPS1") (pin "22") (pinfunction "RESERVED5_22") (pintype "bidirectional"))
    )
    (net (code "53") (name "/GPS1XSTB") (class "Default")
      (node (ref "CY8C5868AXI-LP035") (pin "23") (pinfunction "P1_3_TDO_SWV_23") (pintype "passive"))
      (node (ref "GPS1") (pin "16") (pinfunction "XSTANDBY_16") (pintype "bidirectional"))
    )
    (net (code "54") (name "/GPS2RXA") (class "Default")
      (node (ref "CY8C5868AXI-LP035") (pin "3") (pinfunction "P2_7_3") (pintype "passive"))
      (node (ref "GPS2") (pin "21") (pinfunction "RXD-A_21") (pintype "bidirectional"))
    )
    (net (code "55") (name "/GPS2RXB") (class "Default")
      (node (ref "CY8C5868AXI-LP035") (pin "4") (pinfunction "P12_4_I2C0_SCL_4") (pintype "passive"))
      (node (ref "GPS2") (pin "20") (pinfunction "RXD-B_20") (pintype "bidirectional"))
    )
    (net (code "56") (name "/GPS2TXA") (class "Default")
      (node (ref "CY8C5868AXI-LP035") (pin "1") (pinfunction "P2_5_1") (pintype "passive"))
      (node (ref "GPS2") (pin "23") (pinfunction "TXD-A_23") (pintype "bidirectional"))
    )
    (net (code "57") (name "/GPS2TXB") (class "Default")
      (node (ref "CY8C5868AXI-LP035") (pin "2") (pinfunction "P2_6_2") (pintype "passive"))
      (node (ref "GPS2") (pin "22") (pinfunction "RESERVED5_22") (pintype "bidirectional"))
    )
    (net (code "58") (name "/GPS2XSTB") (class "Default")
      (node (ref "CY8C5868AXI-LP035") (pin "5") (pinfunction "P12_5_I2C0_SDA_5") (pintype "passive"))
      (node (ref "GPS2") (pin "16") (pinfunction "XSTANDBY_16") (pintype "bidirectional"))
    )
    (net (code "59") (name "/GPS3RXA") (class "Default")
      (node (ref "CY8C5868AXI-LP035") (pin "8") (pinfunction "P6_6_8") (pintype "passive"))
      (node (ref "GPS3") (pin "21") (pinfunction "RXD-A_21") (pintype "bidirectional"))
    )
    (net (code "60") (name "/GPS3RXB") (class "Default")
      (node (ref "CY8C5868AXI-LP035") (pin "9") (pinfunction "P6_7_9") (pintype "passive"))
      (node (ref "GPS3") (pin "20") (pinfunction "RXD-B_20") (pintype "bidirectional"))
    )
    (net (code "61") (name "/GPS3TXA") (class "Default")
      (node (ref "CY8C5868AXI-LP035") (pin "6") (pinfunction "P6_4_6") (pintype "passive"))
      (node (ref "GPS3") (pin "23") (pinfunction "TXD-A_23") (pintype "bidirectional"))
    )
    (net (code "62") (name "/GPS3TXB") (class "Default")
      (node (ref "CY8C5868AXI-LP035") (pin "7") (pinfunction "P6_5_7") (pintype "passive"))
      (node (ref "GPS3") (pin "22") (pinfunction "RESERVED5_22") (pintype "bidirectional"))
    )
    (net (code "63") (name "/GPS3XSTB") (class "Default")
      (node (ref "CY8C5868AXI-LP035") (pin "16") (pinfunction "P5_0_16") (pintype "passive"))
      (node (ref "GPS3") (pin "16") (pinfunction "XSTANDBY_16") (pintype "bidirectional"))
    )
    (net (code "64") (name "/GPS4RXA") (class "Default")
      (node (ref "CY8C5868AXI-LP035") (pin "97") (pinfunction "P2_2_97") (pintype "passive"))
      (node (ref "GPS4") (pin "21") (pinfunction "RXD-A_21") (pintype "bidirectional"))
    )
    (net (code "65") (name "/GPS4RXB") (class "Default")
      (node (ref "CY8C5868AXI-LP035") (pin "98") (pinfunction "P2_3_98") (pintype "passive"))
      (node (ref "GPS4") (pin "20") (pinfunction "RXD-B_20") (pintype "bidirectional"))
    )
    (net (code "66") (name "/GPS4TXA") (class "Default")
      (node (ref "CY8C5868AXI-LP035") (pin "95") (pinfunction "P2_0_95") (pintype "passive"))
      (node (ref "GPS4") (pin "23") (pinfunction "TXD-A_23") (pintype "bidirectional"))
    )
    (net (code "67") (name "/GPS4TXB") (class "Default")
      (node (ref "CY8C5868AXI-LP035") (pin "96") (pinfunction "P2_1_96") (pintype "passive"))
      (node (ref "GPS4") (pin "22") (pinfunction "RESERVED5_22") (pintype "bidirectional"))
    )
    (net (code "68") (name "/GPS4XSTB") (class "Default")
      (node (ref "CY8C5868AXI-LP035") (pin "99") (pinfunction "P2_4_99") (pintype "passive"))
      (node (ref "GPS4") (pin "16") (pinfunction "XSTANDBY_16") (pintype "bidirectional"))
    )
    (net (code "69") (name "/INT1") (class "Default")
      (node (ref "ACC") (pin "12") (pinfunction "INT_12") (pintype "bidirectional"))
      (node (ref "CY8C5868AXI-LP035") (pin "27") (pinfunction "P1_6_27") (pintype "passive"))
    )
    (net (code "70") (name "/MDTX1") (class "Default")
      (node (ref "CY8C5868AXI-LP035") (pin "34") (pinfunction "P5_7_34") (pintype "passive"))
      (node (ref "X2") (pin "1") (pinfunction "S_1") (pintype "passive"))
    )
    (net (code "71") (name "/MDTX2") (class "Default")
      (node (ref "CY8C5868AXI-LP035") (pin "35") (pinfunction "P15_6_DP_35") (pintype "passive"))
      (node (ref "X8") (pin "1") (pinfunction "S_1") (pintype "passive"))
    )
    (net (code "72") (name "/PWREN#") (class "Default")
      (node (ref "CY8C5868AXI-LP035") (pin "74") (pinfunction "P0_3_74") (pintype "passive"))
      (node (ref "USBUART") (pin "14") (pinfunction "CBUS3_14") (pintype "bidirectional"))
    )
    (net (code "73") (name "/RTS#") (class "Default")
      (node (ref "CY8C5868AXI-LP035") (pin "71") (pinfunction "P0_0_71") (pintype "passive"))
      (node (ref "USBUART") (pin "3") (pinfunction "_RTS_3") (pintype "output"))
    )
    (net (code "74") (name "/RX1") (class "Default")
      (node (ref "CY8C5868AXI-LP035") (pin "77") (pinfunction "P0_5_77") (pintype "passive"))
      (node (ref "X15") (pin "1") (pinfunction "S_1") (pintype "passive"))
    )
    (net (code "75") (name "/RX2") (class "Default")
      (node (ref "CY8C5868AXI-LP035") (pin "69") (pinfunction "P4_0_69") (pintype "passive"))
      (node (ref "X16") (pin "1") (pinfunction "S_1") (pintype "passive"))
    )
    (net (code "76") (name "/RX3") (class "Default")
      (node (ref "CY8C5868AXI-LP035") (pin "48") (pinfunction "P3_4_48") (pintype "passive"))
      (node (ref "X17") (pin "1") (pinfunction "S_1") (pintype "passive"))
    )
    (net (code "77") (name "/RX4") (class "Default")
      (node (ref "CY8C5868AXI-LP035") (pin "46") (pinfunction "P3_2_46") (pintype "passive"))
      (node (ref "X18") (pin "1") (pinfunction "S_1") (pintype "passive"))
    )
    (net (code "78") (name "/RXLED") (class "Default")
      (node (ref "R15") (pin "2") (pinfunction "2_2") (pintype "passive"))
      (node (ref "USBUART") (pin "22") (pinfunction "CBUS1_22") (pintype "bidirectional"))
    )
    (net (code "79") (name "/SCLK") (class "Default")
      (node (ref "CY8C5868AXI-LP035") (pin "21") (pinfunction "P1_1_TCK_SWDCK_21") (pintype "passive"))
      (node (ref "X7") (pin "4") (pinfunction "S_4") (pintype "passive"))
    )
    (net (code "80") (name "/SCL_ACC") (class "Default")
      (node (ref "ACC") (pin "23") (pinfunction "SCL/SCLK_23") (pintype "bidirectional"))
      (node (ref "CY8C5868AXI-LP035") (pin "25") (pinfunction "P1_5_NTRST_25") (pintype "passive"))
    )
    (net (code "81") (name "/SDAT") (class "Default")
      (node (ref "CY8C5868AXI-LP035") (pin "20") (pinfunction "P1_0_TMS_SWDIO_20") (pintype "passive"))
      (node (ref "X7") (pin "5") (pinfunction "S_5") (pintype "passive"))
    )
    (net (code "82") (name "/SDA_ACC") (class "Default")
      (node (ref "ACC") (pin "24") (pinfunction "SDA/SDI_24") (pintype "bidirectional"))
      (node (ref "CY8C5868AXI-LP035") (pin "24") (pinfunction "P1_4_TDI_24") (pintype "passive"))
    )
    (net (code "83") (name "/STATUS1") (class "Default")
      (node (ref "CY8C5868AXI-LP035") (pin "44") (pinfunction "P3_0_44") (pintype "passive"))
      (node (ref "PWR1") (pin "A") (pinfunction "A_A") (pintype "passive"))
    )
    (net (code "84") (name "/STATUS2") (class "Default")
      (node (ref "CY8C5868AXI-LP035") (pin "43") (pinfunction "P15_1_MXTLI_43") (pintype "passive"))
      (node (ref "PWR2") (pin "A") (pinfunction "A_A") (pintype "passive"))
    )
    (net (code "85") (name "/STATUS3") (class "Default")
      (node (ref "CY8C5868AXI-LP035") (pin "42") (pinfunction "P15_0_MXTLO_42") (pintype "passive"))
      (node (ref "PWR3") (pin "A") (pinfunction "A_A") (pintype "passive"))
    )
    (net (code "86") (name "/STATUS4") (class "Default")
      (node (ref "CY8C5868AXI-LP035") (pin "36") (pinfunction "P15_7_DM_36") (pintype "passive"))
      (node (ref "PWR4") (pin "A") (pinfunction "A_A") (pintype "passive"))
    )
    (net (code "87") (name "/TX1") (class "Default")
      (node (ref "CY8C5868AXI-LP035") (pin "76") (pinfunction "P0_4_76") (pintype "passive"))
      (node (ref "X15") (pin "2") (pinfunction "S_2") (pintype "passive"))
    )
    (net (code "88") (name "/TX2") (class "Default")
      (node (ref "CY8C5868AXI-LP035") (pin "68") (pinfunction "P12_3_68") (pintype "passive"))
      (node (ref "X16") (pin "2") (pinfunction "S_2") (pintype "passive"))
    )
    (net (code "89") (name "/TX3") (class "Default")
      (node (ref "CY8C5868AXI-LP035") (pin "47") (pinfunction "P3_3_47") (pintype "passive"))
      (node (ref "X17") (pin "2") (pinfunction "S_2") (pintype "passive"))
    )
    (net (code "90") (name "/TX4") (class "Default")
      (node (ref "CY8C5868AXI-LP035") (pin "45") (pinfunction "P3_1_45") (pintype "passive"))
      (node (ref "X18") (pin "2") (pinfunction "S_2") (pintype "passive"))
    )
    (net (code "91") (name "/TXLED") (class "Default")
      (node (ref "R14") (pin "2") (pinfunction "2_2") (pintype "passive"))
      (node (ref "USBUART") (pin "23") (pinfunction "CBUS0_23") (pintype "bidirectional"))
    )
    (net (code "92") (name "/USB_RESET") (class "Default")
      (node (ref "R1") (pin "1") (pinfunction "1_1") (pintype "passive"))
      (node (ref "R2") (pin "2") (pinfunction "2_2") (pintype "passive"))
      (node (ref "USBUART") (pin "19") (pinfunction "_RESET_19") (pintype "input"))
    )
    (net (code "93") (name "/USB_RXD") (class "Default")
      (node (ref "CY8C5868AXI-LP035") (pin "73") (pinfunction "P0_2_73") (pintype "passive"))
      (node (ref "USBUART") (pin "5") (pinfunction "RXD_5") (pintype "input"))
    )
    (net (code "94") (name "/USB_TXD") (class "Default")
      (node (ref "CY8C5868AXI-LP035") (pin "72") (pinfunction "P0_1_72") (pintype "passive"))
      (node (ref "USBUART") (pin "1") (pinfunction "TXD_1") (pintype "output"))
    )
    (net (code "95") (name "/VCCD") (class "Default")
      (node (ref "C10") (pin "1") (pinfunction "1_1") (pintype "passive"))
      (node (ref "CY8C5868AXI-LP035") (pin "39") (pinfunction "VCCD_39") (pintype "passive"))
      (node (ref "CY8C5868AXI-LP035") (pin "86") (pinfunction "VCCD_86") (pintype "passive"))
    )
    (net (code "96") (name "/XRES") (class "Default")
      (node (ref "CY8C5868AXI-LP035") (pin "15") (pinfunction "~{XRES}_15") (pintype "passive"))
      (node (ref "X7") (pin "3") (pinfunction "S_3") (pintype "passive"))
    )
    (net (code "97") (name "GND") (class "Default")
      (node (ref "3.3VREG") (pin "3") (pinfunction "GND1_3") (pintype "bidirectional"))
      (node (ref "3.3VREG") (pin "6") (pinfunction "GND3_6") (pintype "bidirectional"))
      (node (ref "3.3VREG") (pin "7") (pinfunction "GND2_7") (pintype "bidirectional"))
      (node (ref "ACC") (pin "1") (pinfunction "CLKIN_1") (pintype "bidirectional"))
      (node (ref "ACC") (pin "18") (pinfunction "GND_18") (pintype "bidirectional"))
      (node (ref "ACC") (pin "9") (pinfunction "AD0/SDO_9") (pintype "bidirectional"))
      (node (ref "C1") (pin "2") (pinfunction "2_2") (pintype "passive"))
      (node (ref "C10") (pin "2") (pinfunction "2_2") (pintype "passive"))
      (node (ref "C11") (pin "2") (pinfunction "2_2") (pintype "passive"))
      (node (ref "C12") (pin "2") (pinfunction "2_2") (pintype "passive"))
      (node (ref "C14") (pin "2") (pinfunction "2_2") (pintype "passive"))
      (node (ref "C15") (pin "2") (pinfunction "2_2") (pintype "passive"))
      (node (ref "C16") (pin "2") (pinfunction "2_2") (pintype "passive"))
      (node (ref "C17") (pin "2") (pinfunction "2_2") (pintype "passive"))
      (node (ref "C18") (pin "2") (pinfunction "2_2") (pintype "passive"))
      (node (ref "C2") (pin "2") (pinfunction "2_2") (pintype "passive"))
      (node (ref "C20") (pin "2") (pinfunction "2_2") (pintype "passive"))
      (node (ref "C21") (pin "2") (pinfunction "2_2") (pintype "passive"))
      (node (ref "C3") (pin "2") (pinfunction "2_2") (pintype "passive"))
      (node (ref "C4") (pin "2") (pinfunction "2_2") (pintype "passive"))
      (node (ref "C5") (pin "2") (pinfunction "2_2") (pintype "passive"))
      (node (ref "C6") (pin "2") (pinfunction "2_2") (pintype "passive"))
      (node (ref "C7") (pin "2") (pinfunction "2_2") (pintype "passive"))
      (node (ref "C8") (pin "2") (pinfunction "2_2") (pintype "passive"))
      (node (ref "C9") (pin "2") (pinfunction "2_2") (pintype "passive"))
      (node (ref "CY8C5868AXI-LP035") (pin "10") (pinfunction "VSSD_10") (pintype "passive"))
      (node (ref "CY8C5868AXI-LP035") (pin "12") (pinfunction "VSSD_12") (pintype "passive"))
      (node (ref "CY8C5868AXI-LP035") (pin "13") (pinfunction "VSSD_13") (pintype "passive"))
      (node (ref "CY8C5868AXI-LP035") (pin "14") (pinfunction "VSSD_14") (pintype "passive"))
      (node (ref "CY8C5868AXI-LP035") (pin "38") (pinfunction "VSSD_38") (pintype "passive"))
      (node (ref "CY8C5868AXI-LP035") (pin "64") (pinfunction "VSSA_64") (pintype "passive"))
      (node (ref "CY8C5868AXI-LP035") (pin "66") (pinfunction "VSSD_66") (pintype "passive"))
      (node (ref "CY8C5868AXI-LP035") (pin "87") (pinfunction "VSSD_87") (pintype "passive"))
      (node (ref "GPS1") (pin "1") (pinfunction "GND_1") (pintype "bidirectional"))
      (node (ref "GPS1") (pin "13") (pinfunction "GND_13") (pintype "bidirectional"))
      (node (ref "GPS1") (pin "14") (pinfunction "GND_14") (pintype "bidirectional"))
      (node (ref "GPS1") (pin "15") (pinfunction "GND_15") (pintype "bidirectional"))
      (node (ref "GPS1") (pin "2") (pinfunction "GND_2") (pintype "bidirectional"))
      (node (ref "GPS1") (pin "27") (pinfunction "GND_27") (pintype "bidirectional"))
      (node (ref "GPS1") (pin "28") (pinfunction "GND_28") (pintype "bidirectional"))
      (node (ref "GPS1") (pin "4") (pinfunction "GND_4") (pintype "bidirectional"))
      (node (ref "GPS1") (pin "7") (pinfunction "OPEN_7") (pintype "bidirectional"))
      (node (ref "GPS2") (pin "1") (pinfunction "GND_1") (pintype "bidirectional"))
      (node (ref "GPS2") (pin "13") (pinfunction "GND_13") (pintype "bidirectional"))
      (node (ref "GPS2") (pin "14") (pinfunction "GND_14") (pintype "bidirectional"))
      (node (ref "GPS2") (pin "15") (pinfunction "GND_15") (pintype "bidirectional"))
      (node (ref "GPS2") (pin "2") (pinfunction "GND_2") (pintype "bidirectional"))
      (node (ref "GPS2") (pin "27") (pinfunction "GND_27") (pintype "bidirectional"))
      (node (ref "GPS2") (pin "28") (pinfunction "GND_28") (pintype "bidirectional"))
      (node (ref "GPS2") (pin "4") (pinfunction "GND_4") (pintype "bidirectional"))
      (node (ref "GPS2") (pin "7") (pinfunction "OPEN_7") (pintype "bidirectional"))
      (node (ref "GPS3") (pin "1") (pinfunction "GND_1") (pintype "bidirectional"))
      (node (ref "GPS3") (pin "13") (pinfunction "GND_13") (pintype "bidirectional"))
      (node (ref "GPS3") (pin "14") (pinfunction "GND_14") (pintype "bidirectional"))
      (node (ref "GPS3") (pin "15") (pinfunction "GND_15") (pintype "bidirectional"))
      (node (ref "GPS3") (pin "2") (pinfunction "GND_2") (pintype "bidirectional"))
      (node (ref "GPS3") (pin "27") (pinfunction "GND_27") (pintype "bidirectional"))
      (node (ref "GPS3") (pin "28") (pinfunction "GND_28") (pintype "bidirectional"))
      (node (ref "GPS3") (pin "4") (pinfunction "GND_4") (pintype "bidirectional"))
      (node (ref "GPS3") (pin "7") (pinfunction "OPEN_7") (pintype "bidirectional"))
      (node (ref "GPS4") (pin "1") (pinfunction "GND_1") (pintype "bidirectional"))
      (node (ref "GPS4") (pin "13") (pinfunction "GND_13") (pintype "bidirectional"))
      (node (ref "GPS4") (pin "14") (pinfunction "GND_14") (pintype "bidirectional"))
      (node (ref "GPS4") (pin "15") (pinfunction "GND_15") (pintype "bidirectional"))
      (node (ref "GPS4") (pin "2") (pinfunction "GND_2") (pintype "bidirectional"))
      (node (ref "GPS4") (pin "27") (pinfunction "GND_27") (pintype "bidirectional"))
      (node (ref "GPS4") (pin "28") (pinfunction "GND_28") (pintype "bidirectional"))
      (node (ref "GPS4") (pin "4") (pinfunction "GND_4") (pintype "bidirectional"))
      (node (ref "GPS4") (pin "7") (pinfunction "OPEN_7") (pintype "bidirectional"))
      (node (ref "IC1") (pin "GND") (pinfunction "GND_GND") (pintype "input"))
      (node (ref "J1") (pin "2") (pinfunction "2_2") (pintype "passive"))
      (node (ref "J1") (pin "3") (pinfunction "3_3") (pintype "passive"))
      (node (ref "MAGNETO") (pin "11") (pinfunction "GND_11") (pintype "bidirectional"))
      (node (ref "MAGNETO") (pin "9") (pinfunction "GND_9") (pintype "bidirectional"))
      (node (ref "MINIUSB") (pin "1") (pinfunction "1_1") (pintype "passive"))
      (node (ref "PI") (pin "14") (pinfunction "S_14") (pintype "passive"))
      (node (ref "PI") (pin "20") (pinfunction "S_20") (pintype "passive"))
      (node (ref "PI") (pin "25") (pinfunction "S_25") (pintype "passive"))
      (node (ref "PI") (pin "6") (pinfunction "S_6") (pintype "passive"))
      (node (ref "PI") (pin "9") (pinfunction "S_9") (pintype "passive"))
      (node (ref "PWR") (pin "C") (pinfunction "C_C") (pintype "passive"))
      (node (ref "PWR5") (pin "C") (pinfunction "C_C") (pintype "passive"))
      (node (ref "PWR6") (pin "C") (pinfunction "C_C") (pintype "passive"))
      (node (ref "R10") (pin "1") (pinfunction "1_1") (pintype "passive"))
      (node (ref "R11") (pin "1") (pinfunction "1_1") (pintype "passive"))
      (node (ref "R12") (pin "1") (pinfunction "1_1") (pintype "passive"))
      (node (ref "R13") (pin "1") (pinfunction "1_1") (pintype "passive"))
      (node (ref "R2") (pin "1") (pinfunction "1_1") (pintype "passive"))
      (node (ref "R6") (pin "1") (pinfunction "1_1") (pintype "passive"))
      (node (ref "R7") (pin "1") (pinfunction "1_1") (pintype "passive"))
      (node (ref "R8") (pin "1") (pinfunction "1_1") (pintype "passive"))
      (node (ref "R9") (pin "1") (pinfunction "1_1") (pintype "passive"))
      (node (ref "RC") (pin "P$1") (pinfunction "GND_P$1") (pintype "bidirectional"))
      (node (ref "RC") (pin "P$10") (pinfunction "GND_P$10") (pintype "bidirectional"))
      (node (ref "RC") (pin "P$13") (pinfunction "GND_P$13") (pintype "bidirectional"))
      (node (ref "RC") (pin "P$16") (pinfunction "GND_P$16") (pintype "bidirectional"))
      (node (ref "RC") (pin "P$4") (pinfunction "GND_P$4") (pintype "bidirectional"))
      (node (ref "RC") (pin "P$7") (pinfunction "GND_P$7") (pintype "bidirectional"))
      (node (ref "USBUART") (pin "18") (pinfunction "GND2_18") (pintype "power_in"))
      (node (ref "USBUART") (pin "21") (pinfunction "GND3_21") (pintype "power_in"))
      (node (ref "USBUART") (pin "25") (pinfunction "AGND_25") (pintype "power_in"))
      (node (ref "USBUART") (pin "26") (pinfunction "TEST_26") (pintype "input"))
      (node (ref "USBUART") (pin "7") (pinfunction "GND1_7") (pintype "power_in"))
      (node (ref "X1") (pin "3") (pinfunction "S_3") (pintype "passive"))
      (node (ref "X13") (pin "3") (pinfunction "S_3") (pintype "passive"))
      (node (ref "X14") (pin "3") (pinfunction "S_3") (pintype "passive"))
      (node (ref "X15") (pin "4") (pinfunction "S_4") (pintype "passive"))
      (node (ref "X16") (pin "4") (pinfunction "S_4") (pintype "passive"))
      (node (ref "X17") (pin "4") (pinfunction "S_4") (pintype "passive"))
      (node (ref "X18") (pin "4") (pinfunction "S_4") (pintype "passive"))
      (node (ref "X2") (pin "3") (pinfunction "S_3") (pintype "passive"))
      (node (ref "X4") (pin "3") (pinfunction "S_3") (pintype "passive"))
      (node (ref "X5") (pin "3") (pinfunction "S_3") (pintype "passive"))
      (node (ref "X6") (pin "3") (pinfunction "S_3") (pintype "passive"))
      (node (ref "X7") (pin "2") (pinfunction "S_2") (pintype "passive"))
      (node (ref "X8") (pin "3") (pinfunction "S_3") (pintype "passive"))
    )
    (net (code "98") (name "Net-(3.3VREG-BYP)") (class "Default")
      (node (ref "3.3VREG") (pin "4") (pinfunction "BYP_4") (pintype "bidirectional"))
      (node (ref "C13") (pin "2") (pinfunction "2_2") (pintype "passive"))
    )
    (net (code "99") (name "Net-(ACC-CPOUT)") (class "Default")
      (node (ref "ACC") (pin "20") (pinfunction "CPOUT_20") (pintype "bidirectional"))
      (node (ref "C18") (pin "1") (pinfunction "1_1") (pintype "passive"))
    )
    (net (code "100") (name "Net-(ACC-REGOUT)") (class "Default")
      (node (ref "ACC") (pin "10") (pinfunction "REGOUT_10") (pintype "bidirectional"))
      (node (ref "C15") (pin "1") (pinfunction "1_1") (pintype "passive"))
    )
    (net (code "101") (name "Net-(CY8C5868AXI-LP035-VCCA)") (class "Default")
      (node (ref "C6") (pin "1") (pinfunction "1_1") (pintype "passive"))
      (node (ref "CY8C5868AXI-LP035") (pin "63") (pinfunction "VCCA_63") (pintype "passive"))
    )
    (net (code "102") (name "Net-(GPS1-RFIN)") (class "Default")
      (node (ref "GPS1") (pin "3") (pinfunction "RFIN_3") (pintype "bidirectional"))
      (node (ref "U$5") (pin "SIG") (pinfunction "SIGNAL_SIG") (pintype "bidirectional"))
    )
    (net (code "103") (name "Net-(GPS2-RFIN)") (class "Default")
      (node (ref "GPS2") (pin "3") (pinfunction "RFIN_3") (pintype "bidirectional"))
      (node (ref "U$7") (pin "SIG") (pinfunction "SIGNAL_SIG") (pintype "bidirectional"))
    )
    (net (code "104") (name "Net-(GPS3-RFIN)") (class "Default")
      (node (ref "GPS3") (pin "3") (pinfunction "RFIN_3") (pintype "bidirectional"))
      (node (ref "U$6") (pin "SIG") (pinfunction "SIGNAL_SIG") (pintype "bidirectional"))
    )
    (net (code "105") (name "Net-(GPS4-RFIN)") (class "Default")
      (node (ref "GPS4") (pin "3") (pinfunction "RFIN_3") (pintype "bidirectional"))
      (node (ref "U$8") (pin "SIG") (pinfunction "SIGNAL_SIG") (pintype "bidirectional"))
    )
    (net (code "106") (name "Net-(MAGNETO-C1)") (class "Default")
      (node (ref "C20") (pin "1") (pinfunction "1_1") (pintype "passive"))
      (node (ref "MAGNETO") (pin "10") (pinfunction "C1_10") (pintype "bidirectional"))
    )
    (net (code "107") (name "Net-(MAGNETO-SETC)") (class "Default")
      (node (ref "C19") (pin "2") (pinfunction "2_2") (pintype "passive"))
      (node (ref "MAGNETO") (pin "12") (pinfunction "SETC_12") (pintype "bidirectional"))
    )
    (net (code "108") (name "Net-(MAGNETO-SETP)") (class "Default")
      (node (ref "C19") (pin "1") (pinfunction "1_1") (pintype "passive"))
      (node (ref "MAGNETO") (pin "8") (pinfunction "SETP_8") (pintype "bidirectional"))
    )
    (net (code "109") (name "Net-(MINIUSB-Pad4)") (class "Default")
      (node (ref "MINIUSB") (pin "4") (pinfunction "4_4") (pintype "passive"))
      (node (ref "MINIUSB") (pin "5") (pinfunction "5_5") (pintype "passive"))
      (node (ref "R1") (pin "2") (pinfunction "2_2") (pintype "passive"))
    )
    (net (code "110") (name "Net-(PWR-PadA)") (class "Default")
      (node (ref "PWR") (pin "A") (pinfunction "A_A") (pintype "passive"))
      (node (ref "R3") (pin "1") (pinfunction "1_1") (pintype "passive"))
    )
    (net (code "111") (name "Net-(PWR1-PadC)") (class "Default")
      (node (ref "PWR1") (pin "C") (pinfunction "C_C") (pintype "passive"))
      (node (ref "R13") (pin "2") (pinfunction "2_2") (pintype "passive"))
    )
    (net (code "112") (name "Net-(PWR2-PadC)") (class "Default")
      (node (ref "PWR2") (pin "C") (pinfunction "C_C") (pintype "passive"))
      (node (ref "R12") (pin "2") (pinfunction "2_2") (pintype "passive"))
    )
    (net (code "113") (name "Net-(PWR3-PadC)") (class "Default")
      (node (ref "PWR3") (pin "C") (pinfunction "C_C") (pintype "passive"))
      (node (ref "R11") (pin "2") (pinfunction "2_2") (pintype "passive"))
    )
    (net (code "114") (name "Net-(PWR4-PadC)") (class "Default")
      (node (ref "PWR4") (pin "C") (pinfunction "C_C") (pintype "passive"))
      (node (ref "R10") (pin "2") (pinfunction "2_2") (pintype "passive"))
    )
    (net (code "115") (name "Net-(PWR5-PadA)") (class "Default")
      (node (ref "PWR5") (pin "A") (pinfunction "A_A") (pintype "passive"))
      (node (ref "R14") (pin "1") (pinfunction "1_1") (pintype "passive"))
    )
    (net (code "116") (name "Net-(PWR6-PadA)") (class "Default")
      (node (ref "PWR6") (pin "A") (pinfunction "A_A") (pintype "passive"))
      (node (ref "R15") (pin "1") (pinfunction "1_1") (pintype "passive"))
    )
    (net (code "117") (name "Net-(USBUART-3V3OUT)") (class "Default")
      (node (ref "C14") (pin "1") (pinfunction "1_1") (pintype "passive"))
      (node (ref "USBUART") (pin "17") (pinfunction "3V3OUT_17") (pintype "output"))
    )
    (net (code "118") (name "unconnected-(CY8C5868AXI-LP035-NC-Pad11)") (class "Default")
      (node (ref "CY8C5868AXI-LP035") (pin "11") (pinfunction "NC_11") (pintype "passive"))
    )
    (net (code "119") (name "unconnected-(CY8C5868AXI-LP035-NC-Pad40)") (class "Default")
      (node (ref "CY8C5868AXI-LP035") (pin "40") (pinfunction "NC_40") (pintype "passive"))
    )
    (net (code "120") (name "unconnected-(CY8C5868AXI-LP035-NC-Pad41)") (class "Default")
      (node (ref "CY8C5868AXI-LP035") (pin "41") (pinfunction "NC_41") (pintype "passive"))
    )
    (net (code "121") (name "unconnected-(CY8C5868AXI-LP035-NC-Pad57)") (class "Default")
      (node (ref "CY8C5868AXI-LP035") (pin "57") (pinfunction "NC_57") (pintype "passive"))
    )
    (net (code "122") (name "unconnected-(CY8C5868AXI-LP035-NC-Pad58)") (class "Default")
      (node (ref "CY8C5868AXI-LP035") (pin "58") (pinfunction "NC_58") (pintype "passive"))
    )
    (net (code "123") (name "unconnected-(CY8C5868AXI-LP035-NC-Pad59)") (class "Default")
      (node (ref "CY8C5868AXI-LP035") (pin "59") (pinfunction "NC_59") (pintype "passive"))
    )
    (net (code "124") (name "unconnected-(CY8C5868AXI-LP035-NC-Pad60)") (class "Default")
      (node (ref "CY8C5868AXI-LP035") (pin "60") (pinfunction "NC_60") (pintype "passive"))
    )
    (net (code "125") (name "unconnected-(CY8C5868AXI-LP035-NC-Pad61)") (class "Default")
      (node (ref "CY8C5868AXI-LP035") (pin "61") (pinfunction "NC_61") (pintype "passive"))
    )
    (net (code "126") (name "unconnected-(CY8C5868AXI-LP035-NC-Pad62)") (class "Default")
      (node (ref "CY8C5868AXI-LP035") (pin "62") (pinfunction "NC_62") (pintype "passive"))
    )
    (net (code "127") (name "unconnected-(GPS1-BOOT-Pad10)") (class "Default")
      (node (ref "GPS1") (pin "10") (pinfunction "BOOT_10") (pintype "bidirectional"))
    )
    (net (code "128") (name "unconnected-(GPS1-LNA-Pad5)") (class "Default")
      (node (ref "GPS1") (pin "5") (pinfunction "LNA_5") (pintype "bidirectional"))
    )
    (net (code "129") (name "unconnected-(GPS1-PPS-Pad19)") (class "Default")
      (node (ref "GPS1") (pin "19") (pinfunction "PPS_19") (pintype "bidirectional"))
    )
    (net (code "130") (name "unconnected-(GPS1-RESERVED1-Pad6)") (class "Default")
      (node (ref "GPS1") (pin "6") (pinfunction "RESERVED1_6") (pintype "bidirectional"))
    )
    (net (code "131") (name "unconnected-(GPS1-RESERVED2-Pad9)") (class "Default")
      (node (ref "GPS1") (pin "9") (pinfunction "RESERVED2_9") (pintype "bidirectional"))
    )
    (net (code "132") (name "unconnected-(GPS1-RESERVED3-Pad17)") (class "Default")
      (node (ref "GPS1") (pin "17") (pinfunction "RESERVED3_17") (pintype "bidirectional"))
    )
    (net (code "133") (name "unconnected-(GPS1-RESERVED4-Pad18)") (class "Default")
      (node (ref "GPS1") (pin "18") (pinfunction "RESERVED4_18") (pintype "bidirectional"))
    )
    (net (code "134") (name "unconnected-(GPS1-RESERVED6-Pad25)") (class "Default")
      (node (ref "GPS1") (pin "25") (pinfunction "RESERVED6_25") (pintype "bidirectional"))
    )
    (net (code "135") (name "unconnected-(GPS1-RESERVED7-Pad26)") (class "Default")
      (node (ref "GPS1") (pin "26") (pinfunction "RESERVED7_26") (pintype "bidirectional"))
    )
    (net (code "136") (name "unconnected-(GPS1-SHORT-Pad8)") (class "Default")
      (node (ref "GPS1") (pin "8") (pinfunction "SHORT_8") (pintype "bidirectional"))
    )
    (net (code "137") (name "unconnected-(GPS1-TXD-B-Pad24)") (class "Default")
      (node (ref "GPS1") (pin "24") (pinfunction "TXD-B_24") (pintype "bidirectional"))
    )
    (net (code "138") (name "unconnected-(GPS1-XRESET-Pad11)") (class "Default")
      (node (ref "GPS1") (pin "11") (pinfunction "XRESET_11") (pintype "bidirectional"))
    )
    (net (code "139") (name "unconnected-(GPS2-BOOT-Pad10)") (class "Default")
      (node (ref "GPS2") (pin "10") (pinfunction "BOOT_10") (pintype "bidirectional"))
    )
    (net (code "140") (name "unconnected-(GPS2-LNA-Pad5)") (class "Default")
      (node (ref "GPS2") (pin "5") (pinfunction "LNA_5") (pintype "bidirectional"))
    )
    (net (code "141") (name "unconnected-(GPS2-PPS-Pad19)") (class "Default")
      (node (ref "GPS2") (pin "19") (pinfunction "PPS_19") (pintype "bidirectional"))
    )
    (net (code "142") (name "unconnected-(GPS2-RESERVED1-Pad6)") (class "Default")
      (node (ref "GPS2") (pin "6") (pinfunction "RESERVED1_6") (pintype "bidirectional"))
    )
    (net (code "143") (name "unconnected-(GPS2-RESERVED2-Pad9)") (class "Default")
      (node (ref "GPS2") (pin "9") (pinfunction "RESERVED2_9") (pintype "bidirectional"))
    )
    (net (code "144") (name "unconnected-(GPS2-RESERVED3-Pad17)") (class "Default")
      (node (ref "GPS2") (pin "17") (pinfunction "RESERVED3_17") (pintype "bidirectional"))
    )
    (net (code "145") (name "unconnected-(GPS2-RESERVED4-Pad18)") (class "Default")
      (node (ref "GPS2") (pin "18") (pinfunction "RESERVED4_18") (pintype "bidirectional"))
    )
    (net (code "146") (name "unconnected-(GPS2-RESERVED6-Pad25)") (class "Default")
      (node (ref "GPS2") (pin "25") (pinfunction "RESERVED6_25") (pintype "bidirectional"))
    )
    (net (code "147") (name "unconnected-(GPS2-RESERVED7-Pad26)") (class "Default")
      (node (ref "GPS2") (pin "26") (pinfunction "RESERVED7_26") (pintype "bidirectional"))
    )
    (net (code "148") (name "unconnected-(GPS2-SHORT-Pad8)") (class "Default")
      (node (ref "GPS2") (pin "8") (pinfunction "SHORT_8") (pintype "bidirectional"))
    )
    (net (code "149") (name "unconnected-(GPS2-TXD-B-Pad24)") (class "Default")
      (node (ref "GPS2") (pin "24") (pinfunction "TXD-B_24") (pintype "bidirectional"))
    )
    (net (code "150") (name "unconnected-(GPS2-XRESET-Pad11)") (class "Default")
      (node (ref "GPS2") (pin "11") (pinfunction "XRESET_11") (pintype "bidirectional"))
    )
    (net (code "151") (name "unconnected-(GPS3-BOOT-Pad10)") (class "Default")
      (node (ref "GPS3") (pin "10") (pinfunction "BOOT_10") (pintype "bidirectional"))
    )
    (net (code "152") (name "unconnected-(GPS3-LNA-Pad5)") (class "Default")
      (node (ref "GPS3") (pin "5") (pinfunction "LNA_5") (pintype "bidirectional"))
    )
    (net (code "153") (name "unconnected-(GPS3-PPS-Pad19)") (class "Default")
      (node (ref "GPS3") (pin "19") (pinfunction "PPS_19") (pintype "bidirectional"))
    )
    (net (code "154") (name "unconnected-(GPS3-RESERVED1-Pad6)") (class "Default")
      (node (ref "GPS3") (pin "6") (pinfunction "RESERVED1_6") (pintype "bidirectional"))
    )
    (net (code "155") (name "unconnected-(GPS3-RESERVED2-Pad9)") (class "Default")
      (node (ref "GPS3") (pin "9") (pinfunction "RESERVED2_9") (pintype "bidirectional"))
    )
    (net (code "156") (name "unconnected-(GPS3-RESERVED3-Pad17)") (class "Default")
      (node (ref "GPS3") (pin "17") (pinfunction "RESERVED3_17") (pintype "bidirectional"))
    )
    (net (code "157") (name "unconnected-(GPS3-RESERVED4-Pad18)") (class "Default")
      (node (ref "GPS3") (pin "18") (pinfunction "RESERVED4_18") (pintype "bidirectional"))
    )
    (net (code "158") (name "unconnected-(GPS3-RESERVED6-Pad25)") (class "Default")
      (node (ref "GPS3") (pin "25") (pinfunction "RESERVED6_25") (pintype "bidirectional"))
    )
    (net (code "159") (name "unconnected-(GPS3-RESERVED7-Pad26)") (class "Default")
      (node (ref "GPS3") (pin "26") (pinfunction "RESERVED7_26") (pintype "bidirectional"))
    )
    (net (code "160") (name "unconnected-(GPS3-SHORT-Pad8)") (class "Default")
      (node (ref "GPS3") (pin "8") (pinfunction "SHORT_8") (pintype "bidirectional"))
    )
    (net (code "161") (name "unconnected-(GPS3-TXD-B-Pad24)") (class "Default")
      (node (ref "GPS3") (pin "24") (pinfunction "TXD-B_24") (pintype "bidirectional"))
    )
    (net (code "162") (name "unconnected-(GPS3-XRESET-Pad11)") (class "Default")
      (node (ref "GPS3") (pin "11") (pinfunction "XRESET_11") (pintype "bidirectional"))
    )
    (net (code "163") (name "unconnected-(GPS4-BOOT-Pad10)") (class "Default")
      (node (ref "GPS4") (pin "10") (pinfunction "BOOT_10") (pintype "bidirectional"))
    )
    (net (code "164") (name "unconnected-(GPS4-LNA-Pad5)") (class "Default")
      (node (ref "GPS4") (pin "5") (pinfunction "LNA_5") (pintype "bidirectional"))
    )
    (net (code "165") (name "unconnected-(GPS4-PPS-Pad19)") (class "Default")
      (node (ref "GPS4") (pin "19") (pinfunction "PPS_19") (pintype "bidirectional"))
    )
    (net (code "166") (name "unconnected-(GPS4-RESERVED1-Pad6)") (class "Default")
      (node (ref "GPS4") (pin "6") (pinfunction "RESERVED1_6") (pintype "bidirectional"))
    )
    (net (code "167") (name "unconnected-(GPS4-RESERVED2-Pad9)") (class "Default")
      (node (ref "GPS4") (pin "9") (pinfunction "RESERVED2_9") (pintype "bidirectional"))
    )
    (net (code "168") (name "unconnected-(GPS4-RESERVED3-Pad17)") (class "Default")
      (node (ref "GPS4") (pin "17") (pinfunction "RESERVED3_17") (pintype "bidirectional"))
    )
    (net (code "169") (name "unconnected-(GPS4-RESERVED4-Pad18)") (class "Default")
      (node (ref "GPS4") (pin "18") (pinfunction "RESERVED4_18") (pintype "bidirectional"))
    )
    (net (code "170") (name "unconnected-(GPS4-RESERVED6-Pad25)") (class "Default")
      (node (ref "GPS4") (pin "25") (pinfunction "RESERVED6_25") (pintype "bidirectional"))
    )
    (net (code "171") (name "unconnected-(GPS4-RESERVED7-Pad26)") (class "Default")
      (node (ref "GPS4") (pin "26") (pinfunction "RESERVED7_26") (pintype "bidirectional"))
    )
    (net (code "172") (name "unconnected-(GPS4-SHORT-Pad8)") (class "Default")
      (node (ref "GPS4") (pin "8") (pinfunction "SHORT_8") (pintype "bidirectional"))
    )
    (net (code "173") (name "unconnected-(GPS4-TXD-B-Pad24)") (class "Default")
      (node (ref "GPS4") (pin "24") (pinfunction "TXD-B_24") (pintype "bidirectional"))
    )
    (net (code "174") (name "unconnected-(GPS4-XRESET-Pad11)") (class "Default")
      (node (ref "GPS4") (pin "11") (pinfunction "XRESET_11") (pintype "bidirectional"))
    )
    (net (code "175") (name "unconnected-(MAGNETO-DRDY-Pad15)") (class "Default")
      (node (ref "MAGNETO") (pin "15") (pinfunction "DRDY_15") (pintype "bidirectional"))
    )
    (net (code "176") (name "unconnected-(MAGNETO-NC-Pad3)") (class "Default")
      (node (ref "MAGNETO") (pin "3") (pinfunction "NC_3") (pintype "bidirectional"))
    )
    (net (code "177") (name "unconnected-(MAGNETO-NC-Pad5)") (class "Default")
      (node (ref "MAGNETO") (pin "5") (pinfunction "NC_5") (pintype "bidirectional"))
    )
    (net (code "178") (name "unconnected-(MAGNETO-NC-Pad6)") (class "Default")
      (node (ref "MAGNETO") (pin "6") (pinfunction "NC_6") (pintype "bidirectional"))
    )
    (net (code "179") (name "unconnected-(MAGNETO-NC-Pad7)") (class "Default")
      (node (ref "MAGNETO") (pin "7") (pinfunction "NC_7") (pintype "bidirectional"))
    )
    (net (code "180") (name "unconnected-(MAGNETO-NC-Pad14)") (class "Default")
      (node (ref "MAGNETO") (pin "14") (pinfunction "NC_14") (pintype "bidirectional"))
    )
    (net (code "181") (name "unconnected-(MINIUSBB-S1-PadM1)") (class "Default")
      (node (ref "MINIUSB") (pin "M1") (pinfunction "S1_M1") (pintype "passive"))
    )
    (net (code "182") (name "unconnected-(MINIUSBB-S2-PadM2)") (class "Default")
      (node (ref "MINIUSB") (pin "M2") (pinfunction "S2_M2") (pintype "passive"))
    )
    (net (code "183") (name "unconnected-(MINIUSBB-S3-PadM3)") (class "Default")
      (node (ref "MINIUSB") (pin "M3") (pinfunction "S3_M3") (pintype "passive"))
    )
    (net (code "184") (name "unconnected-(MINIUSBB-S4-PadM4)") (class "Default")
      (node (ref "MINIUSB") (pin "M4") (pinfunction "S4_M4") (pintype "passive"))
    )
    (net (code "185") (name "unconnected-(USBUART-CBUS2-Pad13)") (class "Default")
      (node (ref "USBUART") (pin "13") (pinfunction "CBUS2_13") (pintype "bidirectional"))
    )
    (net (code "186") (name "unconnected-(USBUART-CBUS4-Pad12)") (class "Default")
      (node (ref "USBUART") (pin "12") (pinfunction "CBUS4_12") (pintype "bidirectional"))
    )
    (net (code "187") (name "unconnected-(USBUART-OSCI-Pad27)") (class "Default")
      (node (ref "USBUART") (pin "27") (pinfunction "OSCI_27") (pintype "input"))
    )
    (net (code "188") (name "unconnected-(USBUART-OSCO-Pad28)") (class "Default")
      (node (ref "USBUART") (pin "28") (pinfunction "OSCO_28") (pintype "output"))
    )
    (net (code "189") (name "unconnected-(USBUART-_DCD-Pad10)") (class "Default")
      (node (ref "USBUART") (pin "10") (pinfunction "_DCD_10") (pintype "input"))
    )
    (net (code "190") (name "unconnected-(USBUART-_DSR-Pad9)") (class "Default")
      (node (ref "USBUART") (pin "9") (pinfunction "_DSR_9") (pintype "input"))
    )
    (net (code "191") (name "unconnected-(USBUART-_DTR-Pad2)") (class "Default")
      (node (ref "USBUART") (pin "2") (pinfunction "_DTR_2") (pintype "output"))
    )
    (net (code "192") (name "unconnected-(USBUART-_RI-Pad6)") (class "Default")
      (node (ref "USBUART") (pin "6") (pinfunction "_RI_6") (pintype "input"))
    )
  )
)
